# vsBenchPowerSupply.net
KiCad netlist of a schematic drawn in EAGLE
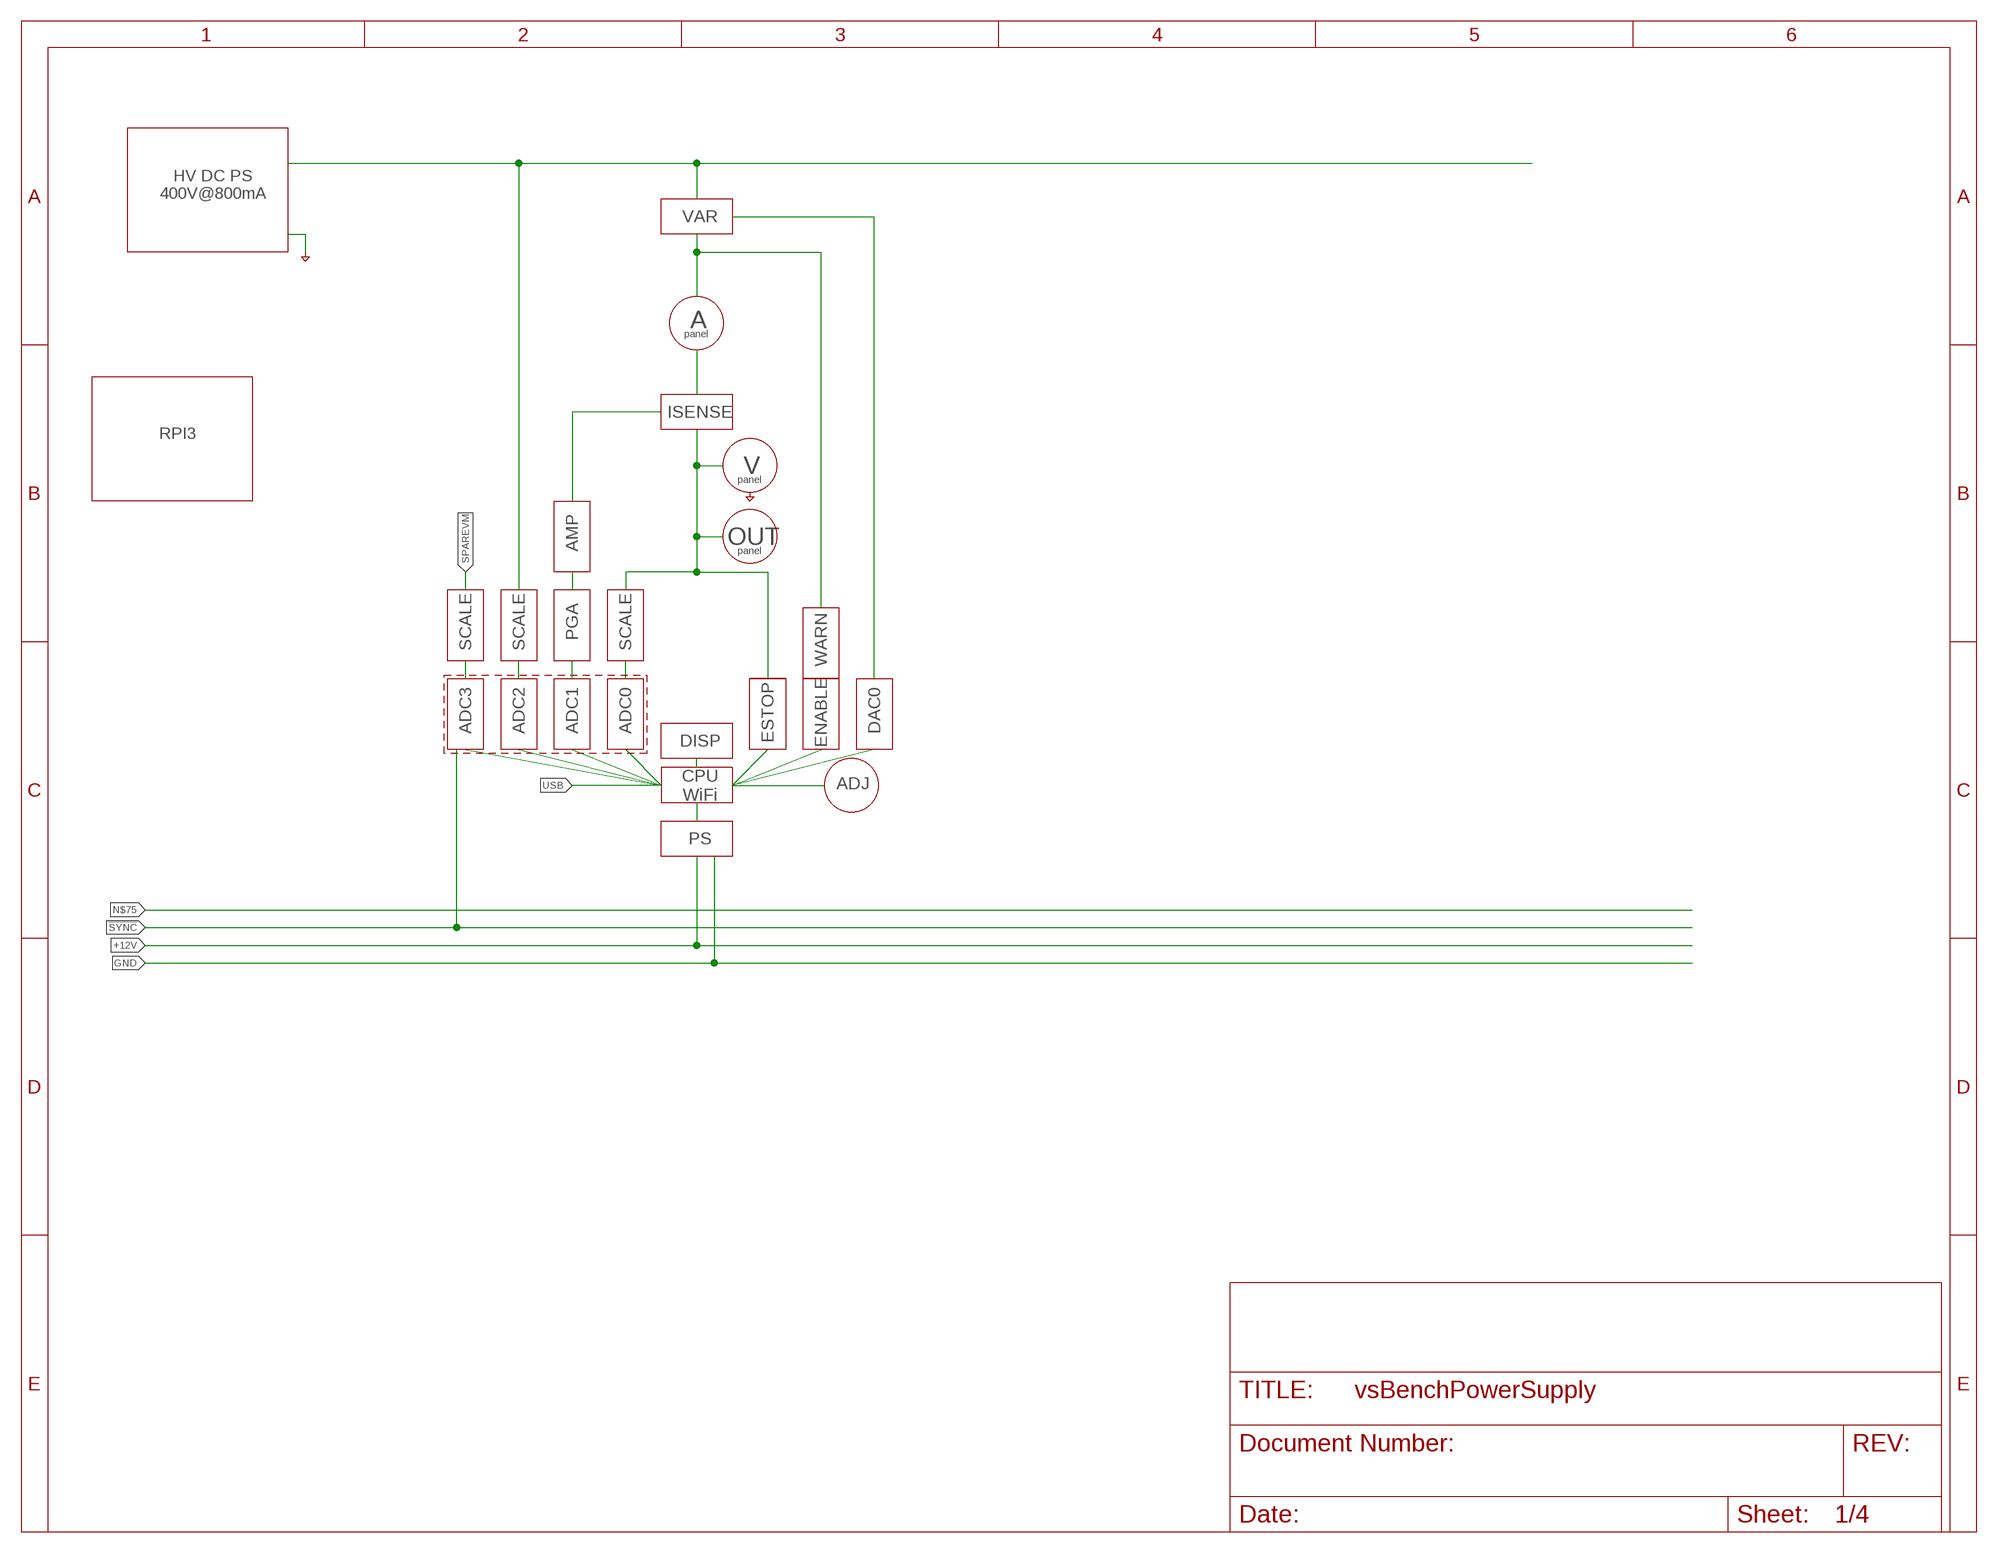
[diagram p0: schematic, sheet 1]
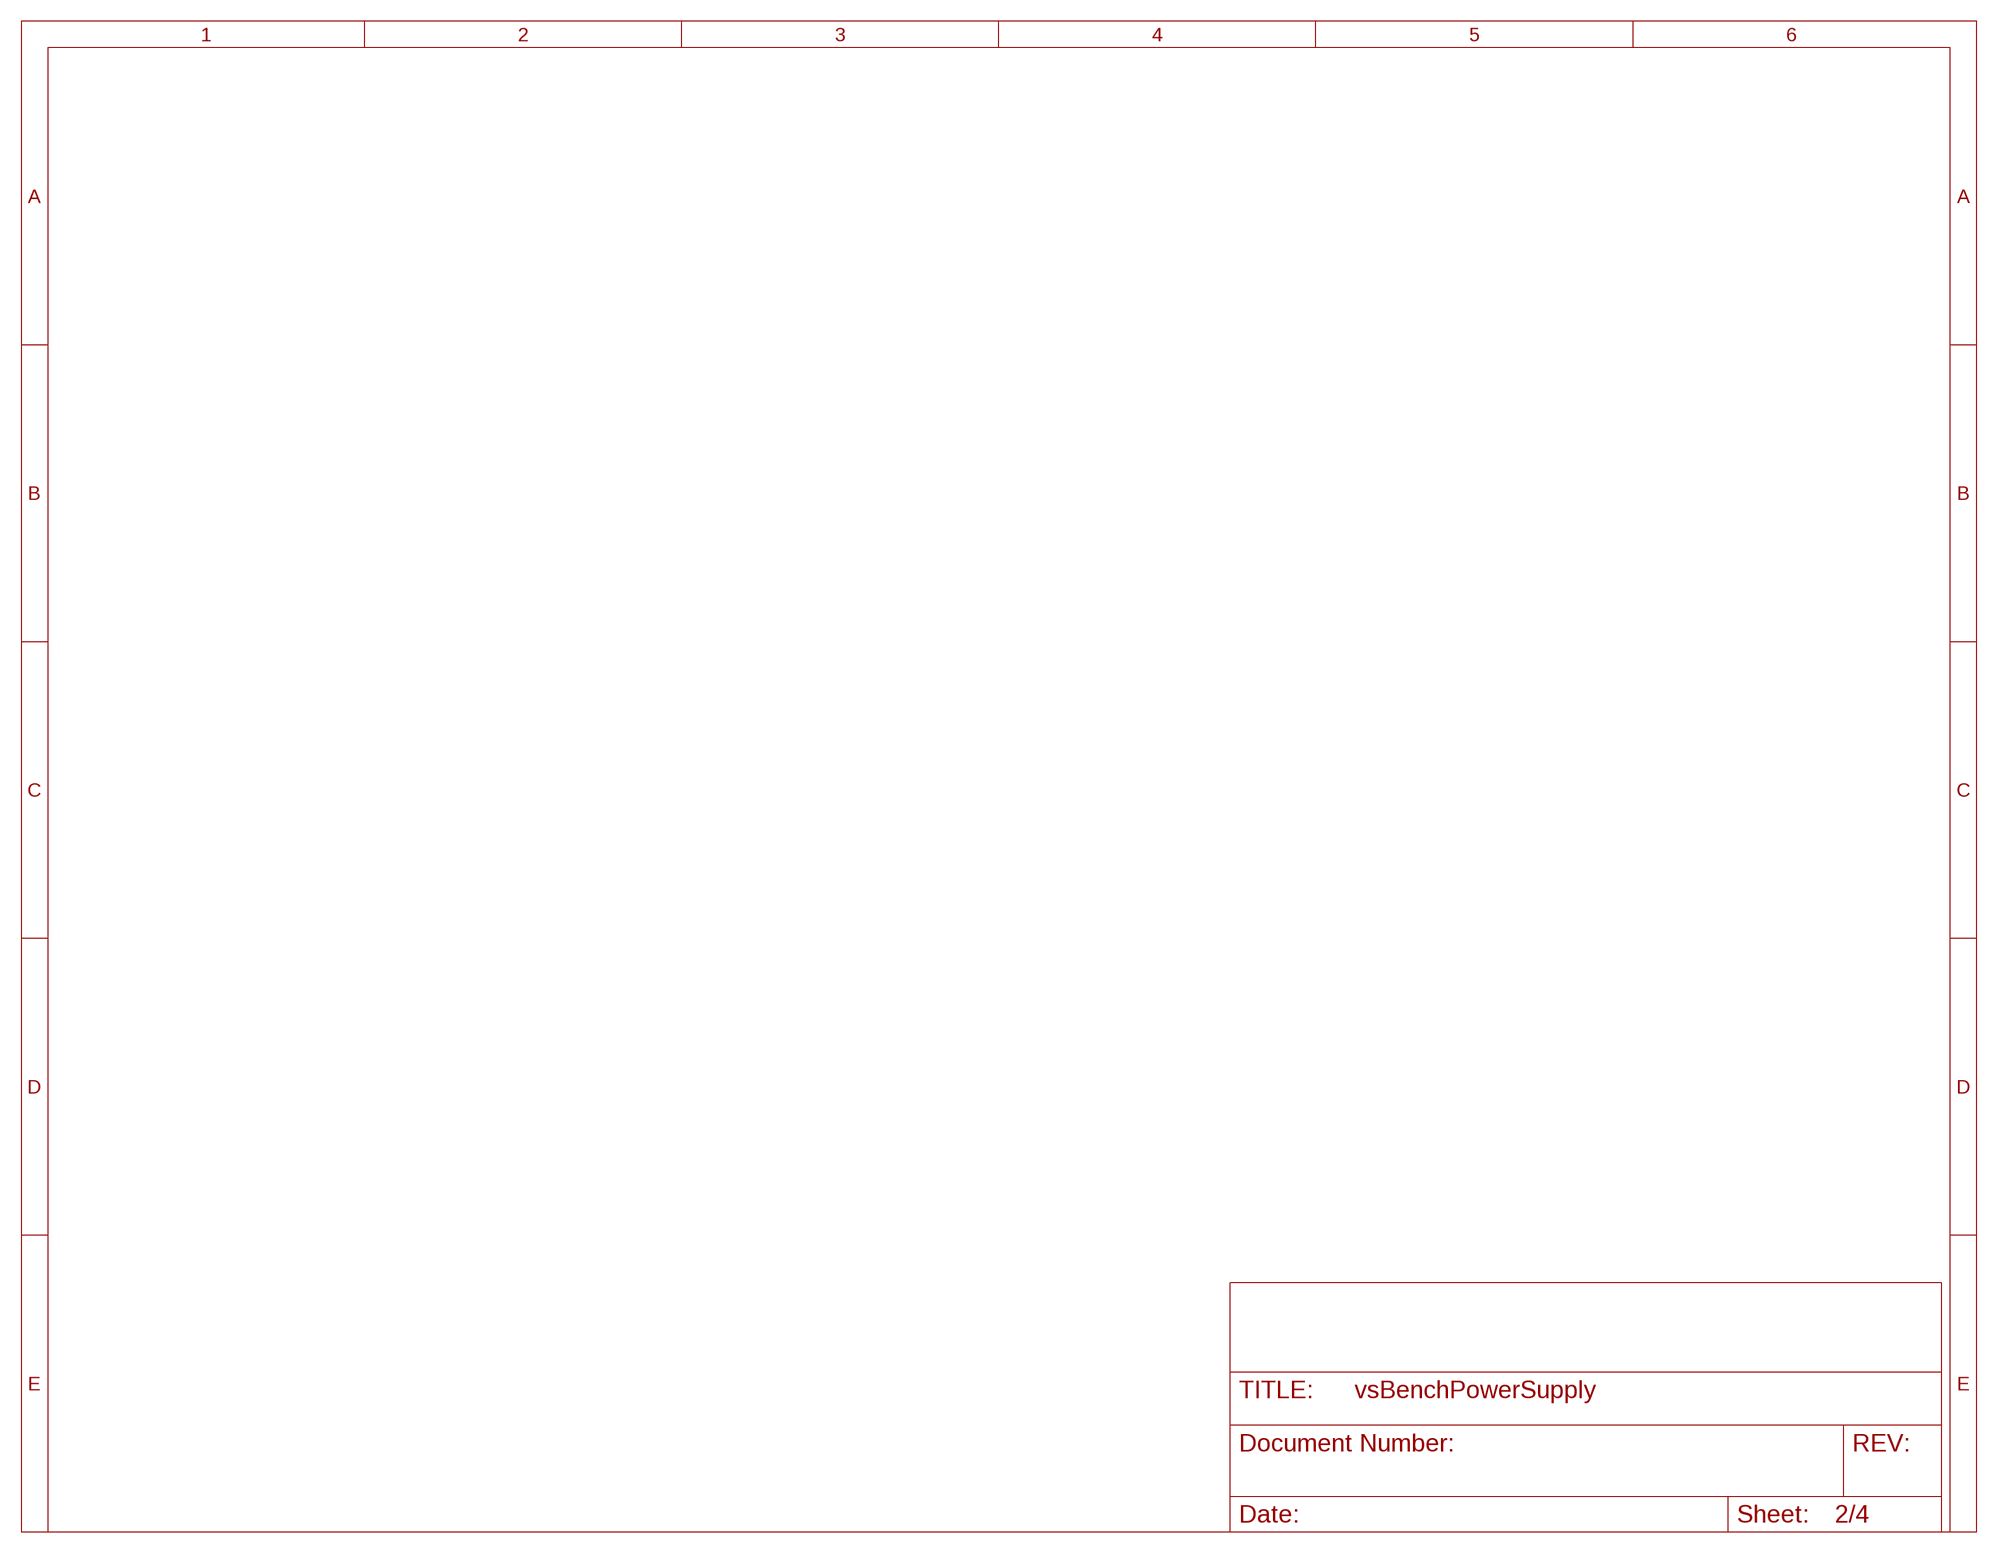
[diagram p1: schematic, sheet 2]
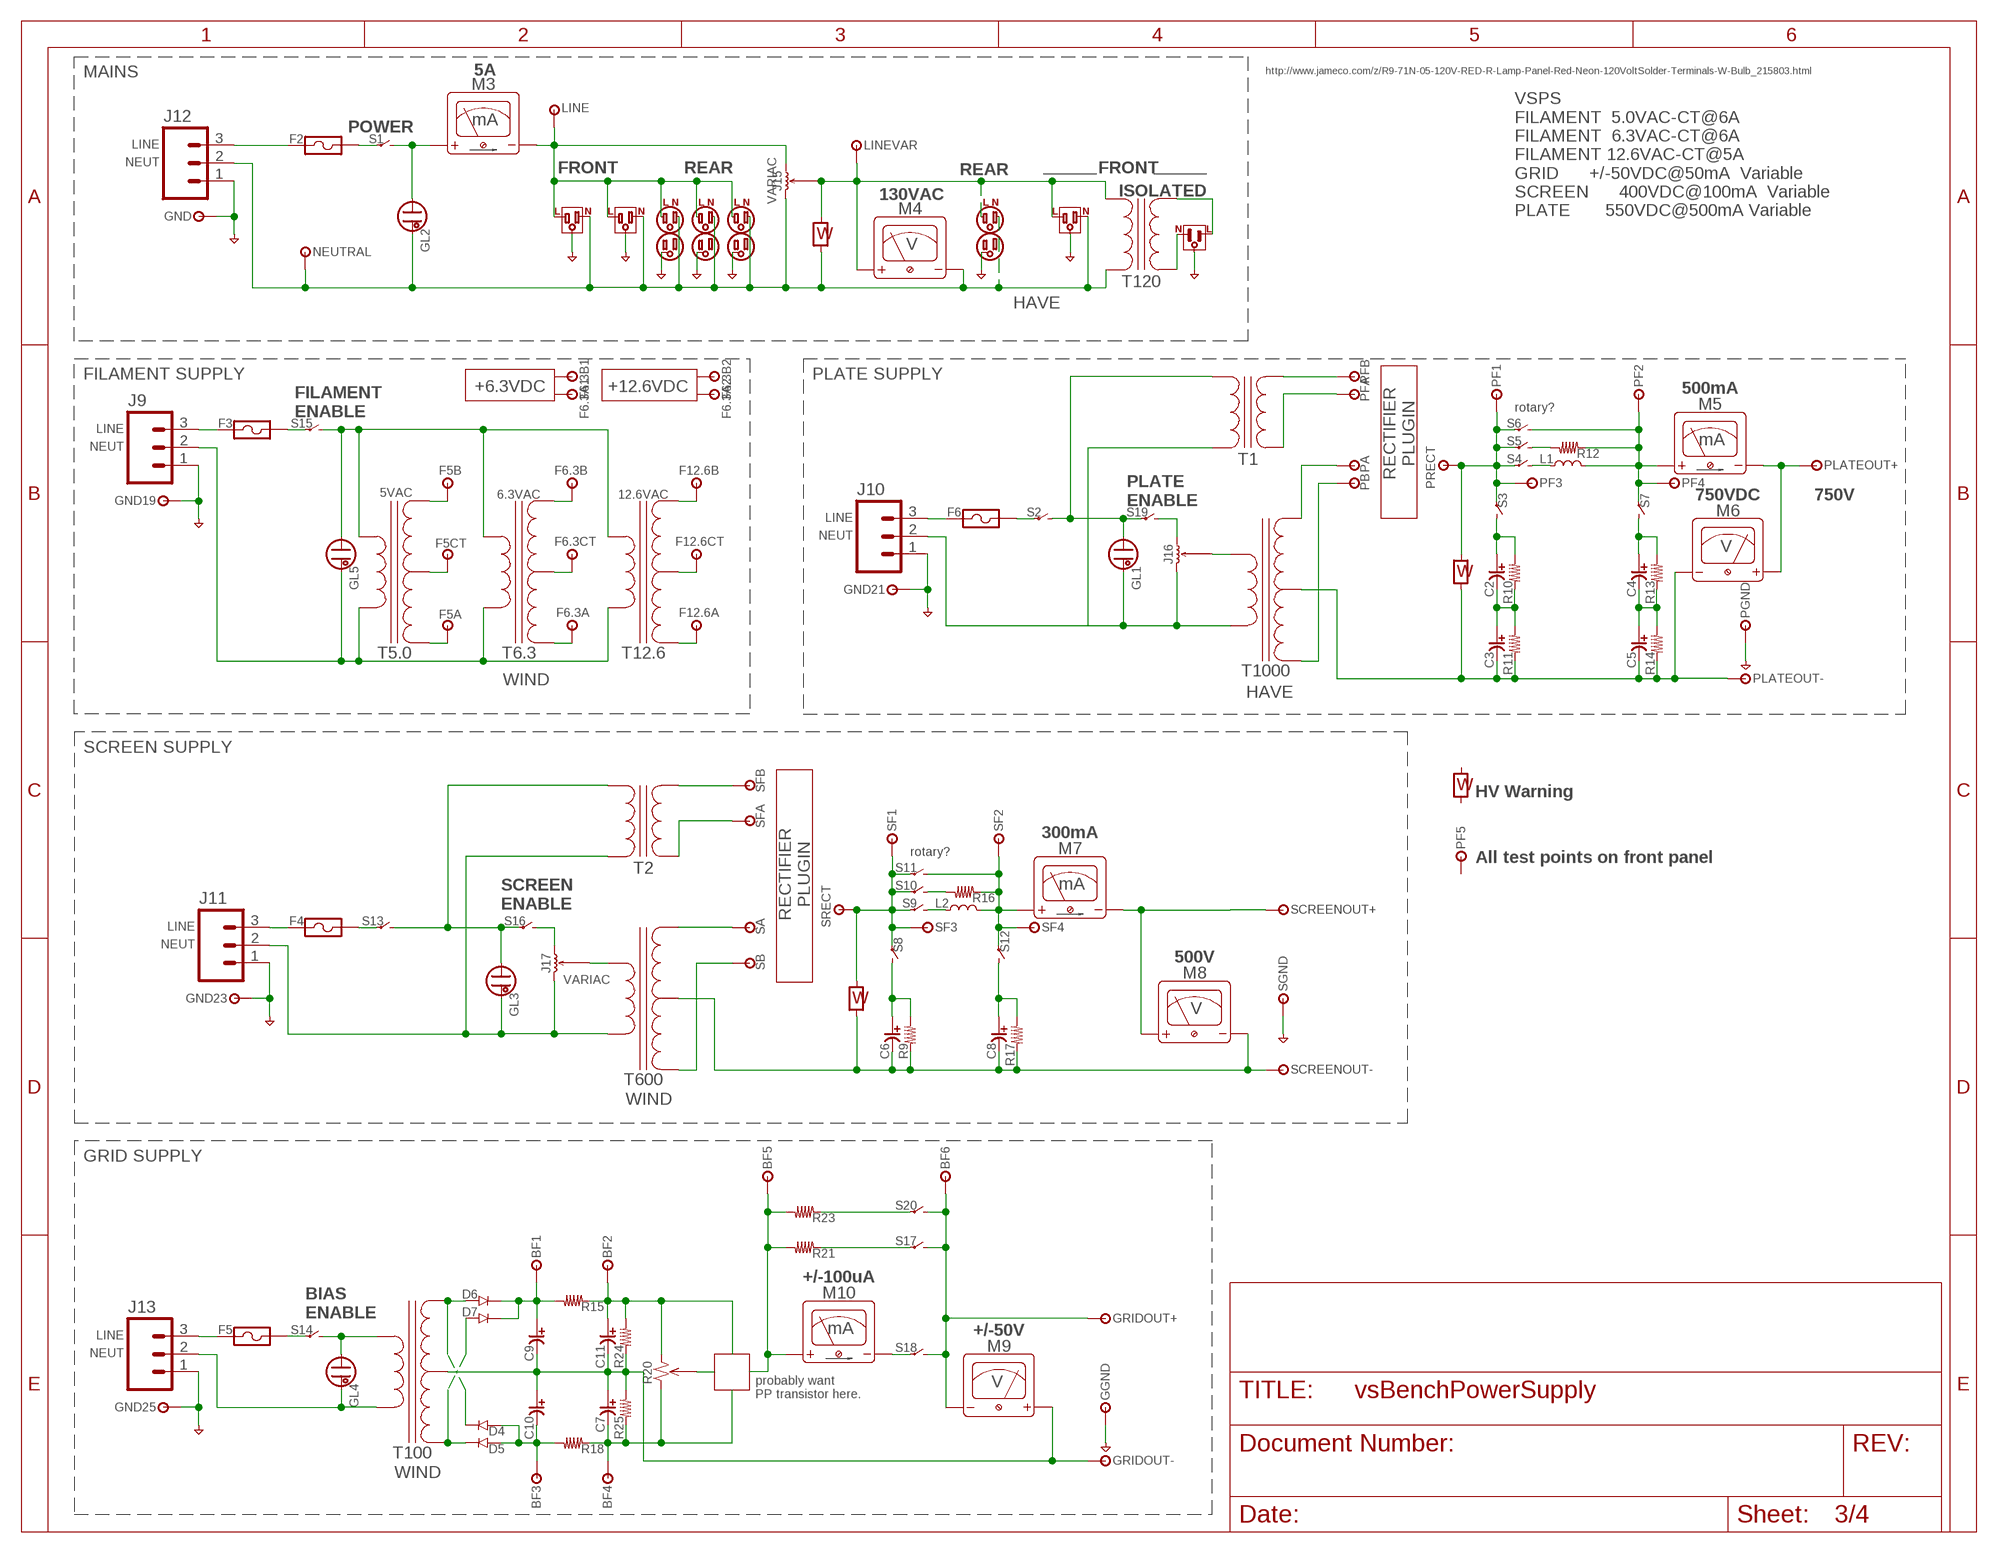
[diagram p2: schematic, sheet 3]
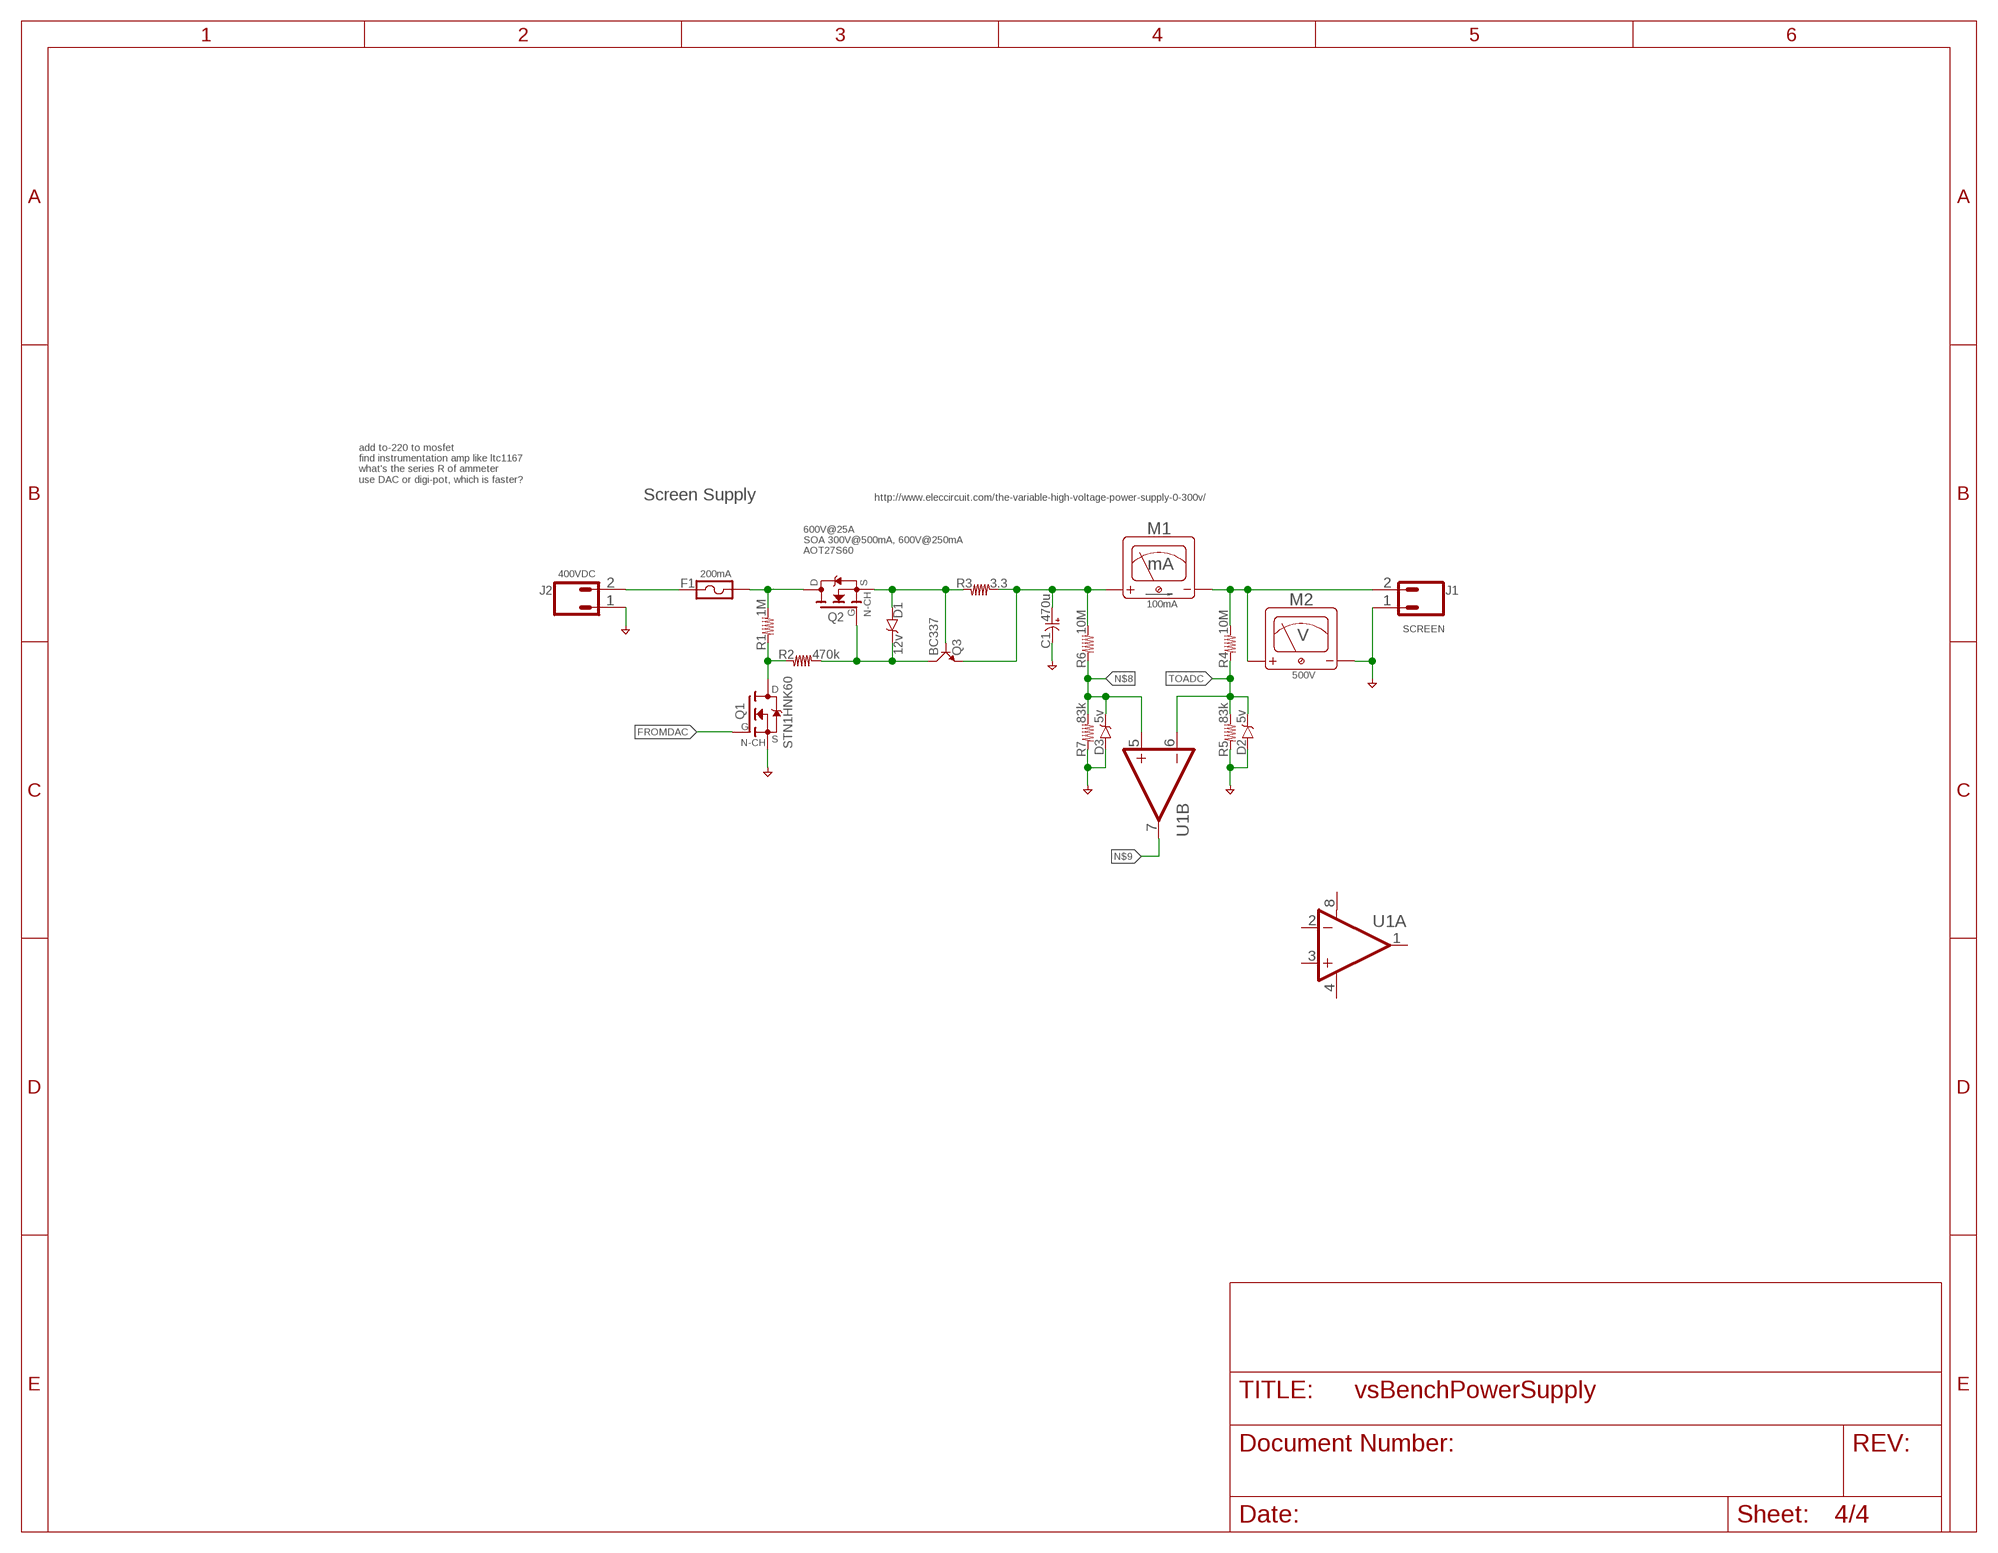
[diagram p3: schematic, sheet 4]

(export (version "E")
  (design (tool "Eeschema 10.0.6"))
  (components
    (comp (ref "BF1")
      (value "TESTPOINTTHRU")
      (footprint "eagle-import:TPTHRU")
      (libsource (lib "eagle-import") (part "TESTPOINTTHRU"))
    )
    (comp (ref "BF2")
      (value "TESTPOINTTHRU")
      (footprint "eagle-import:TPTHRU")
      (libsource (lib "eagle-import") (part "TESTPOINTTHRU"))
    )
    (comp (ref "BF3")
      (value "TESTPOINTTHRU")
      (footprint "eagle-import:TPTHRU")
      (libsource (lib "eagle-import") (part "TESTPOINTTHRU"))
    )
    (comp (ref "BF4")
      (value "TESTPOINTTHRU")
      (footprint "eagle-import:TPTHRU")
      (libsource (lib "eagle-import") (part "TESTPOINTTHRU"))
    )
    (comp (ref "BF5")
      (value "TESTPOINTTHRU")
      (footprint "eagle-import:TPTHRU")
      (libsource (lib "eagle-import") (part "TESTPOINTTHRU"))
    )
    (comp (ref "BF6")
      (value "TESTPOINTTHRU")
      (footprint "eagle-import:TPTHRU")
      (libsource (lib "eagle-import") (part "TESTPOINTTHRU"))
    )
    (comp (ref "C2")
      (value "C-POLARIZED-SMD-E-3MM")
      (footprint "eagle-import:E-3")
      (libsource (lib "eagle-import") (part "C-POLARIZED-SMD-E-3MM"))
    )
    (comp (ref "C3")
      (value "C-POLARIZED-SMD-E-3MM")
      (footprint "eagle-import:E-3")
      (libsource (lib "eagle-import") (part "C-POLARIZED-SMD-E-3MM"))
    )
    (comp (ref "C4")
      (value "C-POLARIZED-SMD-E-3MM")
      (footprint "eagle-import:E-3")
      (libsource (lib "eagle-import") (part "C-POLARIZED-SMD-E-3MM"))
    )
    (comp (ref "C5")
      (value "C-POLARIZED-SMD-E-3MM")
      (footprint "eagle-import:E-3")
      (libsource (lib "eagle-import") (part "C-POLARIZED-SMD-E-3MM"))
    )
    (comp (ref "C6")
      (value "C-POLARIZED-SMD-E-3MM")
      (footprint "eagle-import:E-3")
      (libsource (lib "eagle-import") (part "C-POLARIZED-SMD-E-3MM"))
    )
    (comp (ref "C7")
      (value "C-POLARIZED-SMD-E-3MM")
      (footprint "eagle-import:E-3")
      (libsource (lib "eagle-import") (part "C-POLARIZED-SMD-E-3MM"))
    )
    (comp (ref "C8")
      (value "C-POLARIZED-SMD-E-3MM")
      (footprint "eagle-import:E-3")
      (libsource (lib "eagle-import") (part "C-POLARIZED-SMD-E-3MM"))
    )
    (comp (ref "C9")
      (value "C-POLARIZED-SMD-E-3MM")
      (footprint "eagle-import:E-3")
      (libsource (lib "eagle-import") (part "C-POLARIZED-SMD-E-3MM"))
    )
    (comp (ref "C10")
      (value "C-POLARIZED-SMD-E-3MM")
      (footprint "eagle-import:E-3")
      (libsource (lib "eagle-import") (part "C-POLARIZED-SMD-E-3MM"))
    )
    (comp (ref "C11")
      (value "C-POLARIZED-SMD-E-3MM")
      (footprint "eagle-import:E-3")
      (libsource (lib "eagle-import") (part "C-POLARIZED-SMD-E-3MM"))
    )
    (comp (ref "D4")
      (value "DIODE-1N4148")
      (footprint "eagle-import:DO-35")
      (libsource (lib "eagle-import") (part "DIODE-1N4148"))
    )
    (comp (ref "D5")
      (value "DIODE-1N4148")
      (footprint "eagle-import:DO-35")
      (libsource (lib "eagle-import") (part "DIODE-1N4148"))
    )
    (comp (ref "D6")
      (value "DIODE-1N4148")
      (footprint "eagle-import:DO-35")
      (libsource (lib "eagle-import") (part "DIODE-1N4148"))
    )
    (comp (ref "D7")
      (value "DIODE-1N4148")
      (footprint "eagle-import:DO-35")
      (libsource (lib "eagle-import") (part "DIODE-1N4148"))
    )
    (comp (ref "F2")
      (value "FUSE-HOLDER-3557-2")
      (footprint "eagle-import:3557-2")
      (libsource (lib "eagle-import") (part "FUSE-HOLDER-3557-2"))
    )
    (comp (ref "F3")
      (value "FUSE-HOLDER-3557-2")
      (footprint "eagle-import:3557-2")
      (libsource (lib "eagle-import") (part "FUSE-HOLDER-3557-2"))
    )
    (comp (ref "F4")
      (value "FUSE-HOLDER-3557-2")
      (footprint "eagle-import:3557-2")
      (libsource (lib "eagle-import") (part "FUSE-HOLDER-3557-2"))
    )
    (comp (ref "F5")
      (value "FUSE-HOLDER-3557-2")
      (footprint "eagle-import:3557-2")
      (libsource (lib "eagle-import") (part "FUSE-HOLDER-3557-2"))
    )
    (comp (ref "F5A")
      (value "TESTPOINTTHRU")
      (footprint "eagle-import:TPTHRU")
      (libsource (lib "eagle-import") (part "TESTPOINTTHRU"))
    )
    (comp (ref "F5B")
      (value "TESTPOINTTHRU")
      (footprint "eagle-import:TPTHRU")
      (libsource (lib "eagle-import") (part "TESTPOINTTHRU"))
    )
    (comp (ref "F5CT")
      (value "TESTPOINTTHRU")
      (footprint "eagle-import:TPTHRU")
      (libsource (lib "eagle-import") (part "TESTPOINTTHRU"))
    )
    (comp (ref "F6")
      (value "FUSE-HOLDER-3557-2")
      (footprint "eagle-import:3557-2")
      (libsource (lib "eagle-import") (part "FUSE-HOLDER-3557-2"))
    )
    (comp (ref "F6.3A")
      (value "TESTPOINTTHRU")
      (footprint "eagle-import:TPTHRU")
      (libsource (lib "eagle-import") (part "TESTPOINTTHRU"))
    )
    (comp (ref "F6.3A1")
      (value "TESTPOINTTHRU")
      (footprint "eagle-import:TPTHRU")
      (libsource (lib "eagle-import") (part "TESTPOINTTHRU"))
    )
    (comp (ref "F6.3A2")
      (value "TESTPOINTTHRU")
      (footprint "eagle-import:TPTHRU")
      (libsource (lib "eagle-import") (part "TESTPOINTTHRU"))
    )
    (comp (ref "F6.3B")
      (value "TESTPOINTTHRU")
      (footprint "eagle-import:TPTHRU")
      (libsource (lib "eagle-import") (part "TESTPOINTTHRU"))
    )
    (comp (ref "F6.3B1")
      (value "TESTPOINTTHRU")
      (footprint "eagle-import:TPTHRU")
      (libsource (lib "eagle-import") (part "TESTPOINTTHRU"))
    )
    (comp (ref "F6.3B2")
      (value "TESTPOINTTHRU")
      (footprint "eagle-import:TPTHRU")
      (libsource (lib "eagle-import") (part "TESTPOINTTHRU"))
    )
    (comp (ref "F6.3CT")
      (value "TESTPOINTTHRU")
      (footprint "eagle-import:TPTHRU")
      (libsource (lib "eagle-import") (part "TESTPOINTTHRU"))
    )
    (comp (ref "F12.6A")
      (value "TESTPOINTTHRU")
      (footprint "eagle-import:TPTHRU")
      (libsource (lib "eagle-import") (part "TESTPOINTTHRU"))
    )
    (comp (ref "F12.6B")
      (value "TESTPOINTTHRU")
      (footprint "eagle-import:TPTHRU")
      (libsource (lib "eagle-import") (part "TESTPOINTTHRU"))
    )
    (comp (ref "F12.6CT")
      (value "TESTPOINTTHRU")
      (footprint "eagle-import:TPTHRU")
      (libsource (lib "eagle-import") (part "TESTPOINTTHRU"))
    )
    (comp (ref "GGND")
      (value "TESTPOINTTHRU")
      (footprint "eagle-import:TPTHRU")
      (libsource (lib "eagle-import") (part "TESTPOINTTHRU"))
    )
    (comp (ref "GL1")
      (value "INDICATOR-NEON-BULB-NE2-DRILL")
      (footprint "eagle-import:NE2-NEON-BULB-DRILL")
      (libsource (lib "eagle-import") (part "INDICATOR-NEON-BULB-NE2-DRILL"))
    )
    (comp (ref "GL2")
      (value "INDICATOR-NEON-BULB-NE2-DRILL")
      (footprint "eagle-import:NE2-NEON-BULB-DRILL")
      (libsource (lib "eagle-import") (part "INDICATOR-NEON-BULB-NE2-DRILL"))
    )
    (comp (ref "GL3")
      (value "INDICATOR-NEON-BULB-NE2-DRILL")
      (footprint "eagle-import:NE2-NEON-BULB-DRILL")
      (libsource (lib "eagle-import") (part "INDICATOR-NEON-BULB-NE2-DRILL"))
    )
    (comp (ref "GL4")
      (value "INDICATOR-NEON-BULB-NE2-DRILL")
      (footprint "eagle-import:NE2-NEON-BULB-DRILL")
      (libsource (lib "eagle-import") (part "INDICATOR-NEON-BULB-NE2-DRILL"))
    )
    (comp (ref "GL5")
      (value "INDICATOR-NEON-BULB-NE2-DRILL")
      (footprint "eagle-import:NE2-NEON-BULB-DRILL")
      (libsource (lib "eagle-import") (part "INDICATOR-NEON-BULB-NE2-DRILL"))
    )
    (comp (ref "GND")
      (value "TESTPOINTTHRU")
      (footprint "eagle-import:TPTHRU")
      (libsource (lib "eagle-import") (part "TESTPOINTTHRU"))
    )
    (comp (ref "GND19")
      (value "TESTPOINTTHRU")
      (footprint "eagle-import:TPTHRU")
      (libsource (lib "eagle-import") (part "TESTPOINTTHRU"))
    )
    (comp (ref "GND21")
      (value "TESTPOINTTHRU")
      (footprint "eagle-import:TPTHRU")
      (libsource (lib "eagle-import") (part "TESTPOINTTHRU"))
    )
    (comp (ref "GND23")
      (value "TESTPOINTTHRU")
      (footprint "eagle-import:TPTHRU")
      (libsource (lib "eagle-import") (part "TESTPOINTTHRU"))
    )
    (comp (ref "GND25")
      (value "TESTPOINTTHRU")
      (footprint "eagle-import:TPTHRU")
      (libsource (lib "eagle-import") (part "TESTPOINTTHRU"))
    )
    (comp (ref "GRIDOUT+")
      (value "TESTPOINTTHRU")
      (footprint "eagle-import:TPTHRU")
      (libsource (lib "eagle-import") (part "TESTPOINTTHRU"))
    )
    (comp (ref "GRIDOUT-")
      (value "TESTPOINTTHRU")
      (footprint "eagle-import:TPTHRU")
      (libsource (lib "eagle-import") (part "TESTPOINTTHRU"))
    )
    (comp (ref "J3")
      (value "OUTLET-RECEPTABLE-SINGLE")
      (footprint "eagle-import:CONN-3.81MM-KF2EDG-3")
      (libsource (lib "eagle-import") (part "OUTLET-RECEPTABLE-SINGLE"))
    )
    (comp (ref "J4")
      (value "OUTLET-RECEPTABLE-SINGLE")
      (footprint "eagle-import:CONN-3.81MM-KF2EDG-3")
      (libsource (lib "eagle-import") (part "OUTLET-RECEPTABLE-SINGLE"))
    )
    (comp (ref "J5")
      (value "OUTLET-RECEPTABLE-SINGLE")
      (footprint "eagle-import:CONN-3.81MM-KF2EDG-3")
      (libsource (lib "eagle-import") (part "OUTLET-RECEPTABLE-SINGLE"))
    )
    (comp (ref "J6")
      (value "METER-PANEL-HV-WARNING")
      (footprint "eagle-import:CONN-.100-2")
      (libsource (lib "eagle-import") (part "METER-PANEL-HV-WARNING"))
    )
    (comp (ref "J7")
      (value "METER-PANEL-HV-WARNING")
      (footprint "eagle-import:CONN-.100-2")
      (libsource (lib "eagle-import") (part "METER-PANEL-HV-WARNING"))
    )
    (comp (ref "J8")
      (value "METER-PANEL-HV-WARNING")
      (footprint "eagle-import:CONN-.100-2")
      (libsource (lib "eagle-import") (part "METER-PANEL-HV-WARNING"))
    )
    (comp (ref "J9")
      (value "CONN-03-3.81MM-PLUGIN-SCREW")
      (footprint "eagle-import:CONN-3.81MM-KF2EDG-3")
      (libsource (lib "eagle-import") (part "CONN-03-3.81MM-PLUGIN-SCREW"))
    )
    (comp (ref "J10")
      (value "CONN-03-3.81MM-PLUGIN-SCREW")
      (footprint "eagle-import:CONN-3.81MM-KF2EDG-3")
      (libsource (lib "eagle-import") (part "CONN-03-3.81MM-PLUGIN-SCREW"))
    )
    (comp (ref "J11")
      (value "CONN-03-3.81MM-PLUGIN-SCREW")
      (footprint "eagle-import:CONN-3.81MM-KF2EDG-3")
      (libsource (lib "eagle-import") (part "CONN-03-3.81MM-PLUGIN-SCREW"))
    )
    (comp (ref "J12")
      (value "CONN-03-3.81MM-PLUGIN-SCREW")
      (footprint "eagle-import:CONN-3.81MM-KF2EDG-3")
      (libsource (lib "eagle-import") (part "CONN-03-3.81MM-PLUGIN-SCREW"))
    )
    (comp (ref "J13")
      (value "CONN-03-3.81MM-PLUGIN-SCREW")
      (footprint "eagle-import:CONN-3.81MM-KF2EDG-3")
      (libsource (lib "eagle-import") (part "CONN-03-3.81MM-PLUGIN-SCREW"))
    )
    (comp (ref "J14")
      (value "METER-PANEL-HV-WARNING")
      (footprint "eagle-import:CONN-.100-2")
      (libsource (lib "eagle-import") (part "METER-PANEL-HV-WARNING"))
    )
    (comp (ref "J15")
      (value "VARIAC")
      (footprint "eagle-import:CONN-.100-3")
      (libsource (lib "eagle-import") (part "VARIAC"))
    )
    (comp (ref "J16")
      (value "VARIAC")
      (footprint "eagle-import:CONN-.100-3")
      (libsource (lib "eagle-import") (part "VARIAC"))
    )
    (comp (ref "J17")
      (value "VARIAC")
      (footprint "eagle-import:CONN-.100-3")
      (libsource (lib "eagle-import") (part "VARIAC"))
    )
    (comp (ref "J18")
      (value "OUTLET-RECEPTABLE-SINGLE")
      (footprint "eagle-import:CONN-3.81MM-KF2EDG-3")
      (libsource (lib "eagle-import") (part "OUTLET-RECEPTABLE-SINGLE"))
    )
    (comp (ref "L1")
      (value "INDUCTOR-0805")
      (footprint "eagle-import:R0805")
      (libsource (lib "eagle-import") (part "INDUCTOR-0805"))
    )
    (comp (ref "L2")
      (value "INDUCTOR-0805")
      (footprint "eagle-import:R0805")
      (libsource (lib "eagle-import") (part "INDUCTOR-0805"))
    )
    (comp (ref "LINE")
      (value "TESTPOINTTHRU")
      (footprint "eagle-import:TPTHRU")
      (libsource (lib "eagle-import") (part "TESTPOINTTHRU"))
    )
    (comp (ref "LINEVAR")
      (value "TESTPOINTTHRU")
      (footprint "eagle-import:TPTHRU")
      (libsource (lib "eagle-import") (part "TESTPOINTTHRU"))
    )
    (comp (ref "M3")
      (value "METER-PANEL-ANALOG-CURRENT-PLUGIN-3.81MM")
      (footprint "eagle-import:CONN-3.81MM-KF2EDG-2")
      (libsource (lib "eagle-import") (part "METER-PANEL-ANALOG-CURRENT-PLUGIN-3.81MM"))
    )
    (comp (ref "M4")
      (value "METER-PANEL-ANALOG-VOLTAGE-PLUGIN-3.81MM")
      (footprint "eagle-import:CONN-3.81MM-KF2EDG-2")
      (libsource (lib "eagle-import") (part "METER-PANEL-ANALOG-VOLTAGE-PLUGIN-3.81MM"))
    )
    (comp (ref "M5")
      (value "METER-PANEL-ANALOG-CURRENT-PLUGIN-3.81MM")
      (footprint "eagle-import:CONN-3.81MM-KF2EDG-2")
      (libsource (lib "eagle-import") (part "METER-PANEL-ANALOG-CURRENT-PLUGIN-3.81MM"))
    )
    (comp (ref "M6")
      (value "METER-PANEL-ANALOG-VOLTAGE-PLUGIN-3.81MM")
      (footprint "eagle-import:CONN-3.81MM-KF2EDG-2")
      (libsource (lib "eagle-import") (part "METER-PANEL-ANALOG-VOLTAGE-PLUGIN-3.81MM"))
    )
    (comp (ref "M7")
      (value "METER-PANEL-ANALOG-CURRENT-PLUGIN-3.81MM")
      (footprint "eagle-import:CONN-3.81MM-KF2EDG-2")
      (libsource (lib "eagle-import") (part "METER-PANEL-ANALOG-CURRENT-PLUGIN-3.81MM"))
    )
    (comp (ref "M8")
      (value "METER-PANEL-ANALOG-VOLTAGE-PLUGIN-3.81MM")
      (footprint "eagle-import:CONN-3.81MM-KF2EDG-2")
      (libsource (lib "eagle-import") (part "METER-PANEL-ANALOG-VOLTAGE-PLUGIN-3.81MM"))
    )
    (comp (ref "M9")
      (value "METER-PANEL-ANALOG-VOLTAGE-PLUGIN-3.81MM")
      (footprint "eagle-import:CONN-3.81MM-KF2EDG-2")
      (libsource (lib "eagle-import") (part "METER-PANEL-ANALOG-VOLTAGE-PLUGIN-3.81MM"))
    )
    (comp (ref "M10")
      (value "METER-PANEL-ANALOG-CURRENT-PLUGIN-3.81MM")
      (footprint "eagle-import:CONN-3.81MM-KF2EDG-2")
      (libsource (lib "eagle-import") (part "METER-PANEL-ANALOG-CURRENT-PLUGIN-3.81MM"))
    )
    (comp (ref "NEUTRAL")
      (value "TESTPOINTTHRU")
      (footprint "eagle-import:TPTHRU")
      (libsource (lib "eagle-import") (part "TESTPOINTTHRU"))
    )
    (comp (ref "PA")
      (value "TESTPOINTTHRU")
      (footprint "eagle-import:TPTHRU")
      (libsource (lib "eagle-import") (part "TESTPOINTTHRU"))
    )
    (comp (ref "PB")
      (value "TESTPOINTTHRU")
      (footprint "eagle-import:TPTHRU")
      (libsource (lib "eagle-import") (part "TESTPOINTTHRU"))
    )
    (comp (ref "PF1")
      (value "TESTPOINTTHRU")
      (footprint "eagle-import:TPTHRU")
      (libsource (lib "eagle-import") (part "TESTPOINTTHRU"))
    )
    (comp (ref "PF2")
      (value "TESTPOINTTHRU")
      (footprint "eagle-import:TPTHRU")
      (libsource (lib "eagle-import") (part "TESTPOINTTHRU"))
    )
    (comp (ref "PF3")
      (value "TESTPOINTTHRU")
      (footprint "eagle-import:TPTHRU")
      (libsource (lib "eagle-import") (part "TESTPOINTTHRU"))
    )
    (comp (ref "PF4")
      (value "TESTPOINTTHRU")
      (footprint "eagle-import:TPTHRU")
      (libsource (lib "eagle-import") (part "TESTPOINTTHRU"))
    )
    (comp (ref "PF5")
      (value "TESTPOINTTHRU")
      (footprint "eagle-import:TPTHRU")
      (libsource (lib "eagle-import") (part "TESTPOINTTHRU"))
    )
    (comp (ref "PFA")
      (value "TESTPOINTTHRU")
      (footprint "eagle-import:TPTHRU")
      (libsource (lib "eagle-import") (part "TESTPOINTTHRU"))
    )
    (comp (ref "PFB")
      (value "TESTPOINTTHRU")
      (footprint "eagle-import:TPTHRU")
      (libsource (lib "eagle-import") (part "TESTPOINTTHRU"))
    )
    (comp (ref "PGND")
      (value "TESTPOINTTHRU")
      (footprint "eagle-import:TPTHRU")
      (libsource (lib "eagle-import") (part "TESTPOINTTHRU"))
    )
    (comp (ref "PLATEOUT+")
      (value "TESTPOINTTHRU")
      (footprint "eagle-import:TPTHRU")
      (libsource (lib "eagle-import") (part "TESTPOINTTHRU"))
    )
    (comp (ref "PLATEOUT-")
      (value "TESTPOINTTHRU")
      (footprint "eagle-import:TPTHRU")
      (libsource (lib "eagle-import") (part "TESTPOINTTHRU"))
    )
    (comp (ref "PRECT")
      (value "TESTPOINTTHRU")
      (footprint "eagle-import:TPTHRU")
      (libsource (lib "eagle-import") (part "TESTPOINTTHRU"))
    )
    (comp (ref "R9")
      (value "R-0402")
      (footprint "eagle-import:R0402")
      (libsource (lib "eagle-import") (part "R-0402"))
    )
    (comp (ref "R10")
      (value "R-0402")
      (footprint "eagle-import:R0402")
      (libsource (lib "eagle-import") (part "R-0402"))
    )
    (comp (ref "R11")
      (value "R-0402")
      (footprint "eagle-import:R0402")
      (libsource (lib "eagle-import") (part "R-0402"))
    )
    (comp (ref "R12")
      (value "R-0402")
      (footprint "eagle-import:R0402")
      (libsource (lib "eagle-import") (part "R-0402"))
    )
    (comp (ref "R13")
      (value "R-0402")
      (footprint "eagle-import:R0402")
      (libsource (lib "eagle-import") (part "R-0402"))
    )
    (comp (ref "R14")
      (value "R-0402")
      (footprint "eagle-import:R0402")
      (libsource (lib "eagle-import") (part "R-0402"))
    )
    (comp (ref "R15")
      (value "R-0402")
      (footprint "eagle-import:R0402")
      (libsource (lib "eagle-import") (part "R-0402"))
    )
    (comp (ref "R16")
      (value "R-0402")
      (footprint "eagle-import:R0402")
      (libsource (lib "eagle-import") (part "R-0402"))
    )
    (comp (ref "R17")
      (value "R-0402")
      (footprint "eagle-import:R0402")
      (libsource (lib "eagle-import") (part "R-0402"))
    )
    (comp (ref "R18")
      (value "R-0402")
      (footprint "eagle-import:R0402")
      (libsource (lib "eagle-import") (part "R-0402"))
    )
    (comp (ref "R20")
      (value "POTENTIOMETER")
      (footprint "eagle-import:CONN-.100-3")
      (libsource (lib "eagle-import") (part "POTENTIOMETER"))
    )
    (comp (ref "R21")
      (value "R-0402")
      (footprint "eagle-import:R0402")
      (libsource (lib "eagle-import") (part "R-0402"))
    )
    (comp (ref "R23")
      (value "R-0402")
      (footprint "eagle-import:R0402")
      (libsource (lib "eagle-import") (part "R-0402"))
    )
    (comp (ref "R24")
      (value "R-0402")
      (footprint "eagle-import:R0402")
      (libsource (lib "eagle-import") (part "R-0402"))
    )
    (comp (ref "R25")
      (value "R-0402")
      (footprint "eagle-import:R0402")
      (libsource (lib "eagle-import") (part "R-0402"))
    )
    (comp (ref "S1")
      (value "SWITCH-PANEL-SPST")
      (footprint "eagle-import:CONN-.100-2")
      (libsource (lib "eagle-import") (part "SWITCH-PANEL-SPST"))
    )
    (comp (ref "S2")
      (value "SWITCH-PANEL-SPST")
      (footprint "eagle-import:CONN-.100-2")
      (libsource (lib "eagle-import") (part "SWITCH-PANEL-SPST"))
    )
    (comp (ref "S3")
      (value "SWITCH-PANEL-SPST")
      (footprint "eagle-import:CONN-.100-2")
      (libsource (lib "eagle-import") (part "SWITCH-PANEL-SPST"))
    )
    (comp (ref "S4")
      (value "SWITCH-PANEL-SPST")
      (footprint "eagle-import:CONN-.100-2")
      (libsource (lib "eagle-import") (part "SWITCH-PANEL-SPST"))
    )
    (comp (ref "S5")
      (value "SWITCH-PANEL-SPST")
      (footprint "eagle-import:CONN-.100-2")
      (libsource (lib "eagle-import") (part "SWITCH-PANEL-SPST"))
    )
    (comp (ref "S6")
      (value "SWITCH-PANEL-SPST")
      (footprint "eagle-import:CONN-.100-2")
      (libsource (lib "eagle-import") (part "SWITCH-PANEL-SPST"))
    )
    (comp (ref "S7")
      (value "SWITCH-PANEL-SPST")
      (footprint "eagle-import:CONN-.100-2")
      (libsource (lib "eagle-import") (part "SWITCH-PANEL-SPST"))
    )
    (comp (ref "S8")
      (value "SWITCH-PANEL-SPST")
      (footprint "eagle-import:CONN-.100-2")
      (libsource (lib "eagle-import") (part "SWITCH-PANEL-SPST"))
    )
    (comp (ref "S9")
      (value "SWITCH-PANEL-SPST")
      (footprint "eagle-import:CONN-.100-2")
      (libsource (lib "eagle-import") (part "SWITCH-PANEL-SPST"))
    )
    (comp (ref "S10")
      (value "SWITCH-PANEL-SPST")
      (footprint "eagle-import:CONN-.100-2")
      (libsource (lib "eagle-import") (part "SWITCH-PANEL-SPST"))
    )
    (comp (ref "S11")
      (value "SWITCH-PANEL-SPST")
      (footprint "eagle-import:CONN-.100-2")
      (libsource (lib "eagle-import") (part "SWITCH-PANEL-SPST"))
    )
    (comp (ref "S12")
      (value "SWITCH-PANEL-SPST")
      (footprint "eagle-import:CONN-.100-2")
      (libsource (lib "eagle-import") (part "SWITCH-PANEL-SPST"))
    )
    (comp (ref "S13")
      (value "SWITCH-PANEL-SPST")
      (footprint "eagle-import:CONN-.100-2")
      (libsource (lib "eagle-import") (part "SWITCH-PANEL-SPST"))
    )
    (comp (ref "S14")
      (value "SWITCH-PANEL-SPST")
      (footprint "eagle-import:CONN-.100-2")
      (libsource (lib "eagle-import") (part "SWITCH-PANEL-SPST"))
    )
    (comp (ref "S15")
      (value "SWITCH-PANEL-SPST")
      (footprint "eagle-import:CONN-.100-2")
      (libsource (lib "eagle-import") (part "SWITCH-PANEL-SPST"))
    )
    (comp (ref "S16")
      (value "SWITCH-PANEL-SPST")
      (footprint "eagle-import:CONN-.100-2")
      (libsource (lib "eagle-import") (part "SWITCH-PANEL-SPST"))
    )
    (comp (ref "S17")
      (value "SWITCH-PANEL-SPST")
      (footprint "eagle-import:CONN-.100-2")
      (libsource (lib "eagle-import") (part "SWITCH-PANEL-SPST"))
    )
    (comp (ref "S18")
      (value "SWITCH-PANEL-SPST")
      (footprint "eagle-import:CONN-.100-2")
      (libsource (lib "eagle-import") (part "SWITCH-PANEL-SPST"))
    )
    (comp (ref "S19")
      (value "SWITCH-PANEL-SPST")
      (footprint "eagle-import:CONN-.100-2")
      (libsource (lib "eagle-import") (part "SWITCH-PANEL-SPST"))
    )
    (comp (ref "S20")
      (value "SWITCH-PANEL-SPST")
      (footprint "eagle-import:CONN-.100-2")
      (libsource (lib "eagle-import") (part "SWITCH-PANEL-SPST"))
    )
    (comp (ref "SA")
      (value "TESTPOINTTHRU")
      (footprint "eagle-import:TPTHRU")
      (libsource (lib "eagle-import") (part "TESTPOINTTHRU"))
    )
    (comp (ref "SB")
      (value "TESTPOINTTHRU")
      (footprint "eagle-import:TPTHRU")
      (libsource (lib "eagle-import") (part "TESTPOINTTHRU"))
    )
    (comp (ref "SCREENOUT+")
      (value "TESTPOINTTHRU")
      (footprint "eagle-import:TPTHRU")
      (libsource (lib "eagle-import") (part "TESTPOINTTHRU"))
    )
    (comp (ref "SCREENOUT-")
      (value "TESTPOINTTHRU")
      (footprint "eagle-import:TPTHRU")
      (libsource (lib "eagle-import") (part "TESTPOINTTHRU"))
    )
    (comp (ref "SF1")
      (value "TESTPOINTTHRU")
      (footprint "eagle-import:TPTHRU")
      (libsource (lib "eagle-import") (part "TESTPOINTTHRU"))
    )
    (comp (ref "SF2")
      (value "TESTPOINTTHRU")
      (footprint "eagle-import:TPTHRU")
      (libsource (lib "eagle-import") (part "TESTPOINTTHRU"))
    )
    (comp (ref "SF3")
      (value "TESTPOINTTHRU")
      (footprint "eagle-import:TPTHRU")
      (libsource (lib "eagle-import") (part "TESTPOINTTHRU"))
    )
    (comp (ref "SF4")
      (value "TESTPOINTTHRU")
      (footprint "eagle-import:TPTHRU")
      (libsource (lib "eagle-import") (part "TESTPOINTTHRU"))
    )
    (comp (ref "SFA")
      (value "TESTPOINTTHRU")
      (footprint "eagle-import:TPTHRU")
      (libsource (lib "eagle-import") (part "TESTPOINTTHRU"))
    )
    (comp (ref "SFB")
      (value "TESTPOINTTHRU")
      (footprint "eagle-import:TPTHRU")
      (libsource (lib "eagle-import") (part "TESTPOINTTHRU"))
    )
    (comp (ref "SGND")
      (value "TESTPOINTTHRU")
      (footprint "eagle-import:TPTHRU")
      (libsource (lib "eagle-import") (part "TESTPOINTTHRU"))
    )
    (comp (ref "SRECT")
      (value "TESTPOINTTHRU")
      (footprint "eagle-import:TPTHRU")
      (libsource (lib "eagle-import") (part "TESTPOINTTHRU"))
    )
    (comp (ref "T1")
      (value "TRANSFORMER-2-2")
      (footprint "eagle-import:TRANSFORMER-4-2-G")
      (libsource (lib "eagle-import") (part "TRANSFORMER-2-2"))
    )
    (comp (ref "T2")
      (value "TRANSFORMER-2-2")
      (footprint "eagle-import:TRANSFORMER-4-2-G")
      (libsource (lib "eagle-import") (part "TRANSFORMER-2-2"))
    )
    (comp (ref "T5.0")
      (value "TRANSFORMER-3-2")
      (footprint "eagle-import:CONN-.100-5")
      (libsource (lib "eagle-import") (part "TRANSFORMER-3-2"))
    )
    (comp (ref "T6.3")
      (value "TRANSFORMER-3-2")
      (footprint "eagle-import:CONN-.100-5")
      (libsource (lib "eagle-import") (part "TRANSFORMER-3-2"))
    )
    (comp (ref "T12.6")
      (value "TRANSFORMER-3-2")
      (footprint "eagle-import:CONN-.100-5")
      (libsource (lib "eagle-import") (part "TRANSFORMER-3-2"))
    )
    (comp (ref "T100")
      (value "TRANSFORMER-3-2")
      (footprint "eagle-import:CONN-.100-5")
      (libsource (lib "eagle-import") (part "TRANSFORMER-3-2"))
    )
    (comp (ref "T120")
      (value "TRANSFORMER-2-2")
      (footprint "eagle-import:TRANSFORMER-4-2-G")
      (libsource (lib "eagle-import") (part "TRANSFORMER-2-2"))
    )
    (comp (ref "T600")
      (value "TRANSFORMER-3-2")
      (footprint "eagle-import:CONN-.100-5")
      (libsource (lib "eagle-import") (part "TRANSFORMER-3-2"))
    )
    (comp (ref "T1000")
      (value "TRANSFORMER-3-2")
      (footprint "eagle-import:CONN-.100-5")
      (libsource (lib "eagle-import") (part "TRANSFORMER-3-2"))
    )
    (comp (ref "U$1")
      (value "OUTLET-RECEPTACLE")
      (footprint "eagle-import:CONN-3.81MM-KF2EDG-3")
      (libsource (lib "eagle-import") (part "OUTLET-RECEPTACLE"))
    )
    (comp (ref "U$2")
      (value "OUTLET-RECEPTACLE")
      (footprint "eagle-import:CONN-3.81MM-KF2EDG-3")
      (libsource (lib "eagle-import") (part "OUTLET-RECEPTACLE"))
    )
    (comp (ref "U$3")
      (value "OUTLET-RECEPTACLE")
      (footprint "eagle-import:CONN-3.81MM-KF2EDG-3")
      (libsource (lib "eagle-import") (part "OUTLET-RECEPTACLE"))
    )
    (comp (ref "U$4")
      (value "OUTLET-RECEPTACLE")
      (footprint "eagle-import:CONN-3.81MM-KF2EDG-3")
      (libsource (lib "eagle-import") (part "OUTLET-RECEPTACLE"))
    )
    (comp (ref "C1")
      (value "470u")
      (footprint "eagle-import:E5-10,5")
      (libsource (lib "eagle-import") (part "C-E5-10.5"))
    )
    (comp (ref "D1")
      (value "12v")
      (footprint "eagle-import:SOD-323")
      (libsource (lib "eagle-import") (part "DIODE-ZENER-0805"))
    )
    (comp (ref "D2")
      (value "5v")
      (footprint "eagle-import:SOD-323")
      (libsource (lib "eagle-import") (part "DIODE-ZENER-0805"))
    )
    (comp (ref "D3")
      (value "5v")
      (footprint "eagle-import:SOD-323")
      (libsource (lib "eagle-import") (part "DIODE-ZENER-0805"))
    )
    (comp (ref "F1")
      (value "FUSE-HOLDER-3557-2")
      (footprint "eagle-import:3557-2")
      (libsource (lib "eagle-import") (part "FUSE-HOLDER-3557-2"))
    )
    (comp (ref "J1")
      (value "CONN-02-3.81MM-PLUGIN-SCREW")
      (footprint "eagle-import:CONN-3.81MM-KF2EDG-2")
      (libsource (lib "eagle-import") (part "CONN-02-3.81MM-PLUGIN-SCREW"))
    )
    (comp (ref "J2")
      (value "CONN-02-3.81MM-PLUGIN-SCREW")
      (footprint "eagle-import:CONN-3.81MM-KF2EDG-2")
      (libsource (lib "eagle-import") (part "CONN-02-3.81MM-PLUGIN-SCREW"))
    )
    (comp (ref "M1")
      (value "METER-PANEL-ANALOG-CURRENT-PLUGIN-3.81MM")
      (footprint "eagle-import:CONN-3.81MM-KF2EDG-2")
      (libsource (lib "eagle-import") (part "METER-PANEL-ANALOG-CURRENT-PLUGIN-3.81MM"))
    )
    (comp (ref "M2")
      (value "METER-PANEL-ANALOG-VOLTAGE-PLUGIN-3.81MM")
      (footprint "eagle-import:CONN-3.81MM-KF2EDG-2")
      (libsource (lib "eagle-import") (part "METER-PANEL-ANALOG-VOLTAGE-PLUGIN-3.81MM"))
    )
    (comp (ref "Q1")
      (value "STN1HNK60")
      (footprint "eagle-import:SOT23-3")
      (libsource (lib "eagle-import") (part "FET-NCH-SOT23"))
    )
    (comp (ref "Q2")
      (value "FET-NCH-TO252")
      (footprint "eagle-import:TO252")
      (libsource (lib "eagle-import") (part "FET-NCH-TO252"))
    )
    (comp (ref "Q3")
      (value "BC337")
      (footprint "eagle-import:SOT23-3")
      (libsource (lib "eagle-import") (part "TRANSISTOR_NPNSOT23-3"))
    )
    (comp (ref "R1")
      (value "1M")
      (footprint "eagle-import:R2512")
      (fields (field (name "DESC") "1W"))
      (libsource (lib "eagle-import") (part "R-2512"))
    )
    (comp (ref "R2")
      (value "470k")
      (footprint "eagle-import:R2512")
      (libsource (lib "eagle-import") (part "R-2512"))
    )
    (comp (ref "R3")
      (value "3.3")
      (footprint "eagle-import:R2512")
      (libsource (lib "eagle-import") (part "R-2512"))
    )
    (comp (ref "R4")
      (value "10M")
      (footprint "eagle-import:R2512")
      (fields (field (name "DESC") ".1%"))
      (libsource (lib "eagle-import") (part "R-2512"))
    )
    (comp (ref "R5")
      (value "83k")
      (footprint "eagle-import:R2512")
      (fields (field (name "DESC") ".1%"))
      (libsource (lib "eagle-import") (part "R-2512"))
    )
    (comp (ref "R6")
      (value "10M")
      (footprint "eagle-import:R2512")
      (fields (field (name "DESC") ",1%"))
      (libsource (lib "eagle-import") (part "R-2512"))
    )
    (comp (ref "R7")
      (value "83k")
      (footprint "eagle-import:R2512")
      (fields (field (name "DESC") ".1%"))
      (libsource (lib "eagle-import") (part "R-2512"))
    )
    (comp (ref "U1")
      (value "AMP-OPAMP-DUAL-SO08")
      (footprint "eagle-import:SO08")
      (libsource (lib "eagle-import") (part "AMP-OPAMP-DUAL-SO08"))
    )
  )
  (nets
    (net (code "2") (name "FROMDAC") (class "Default")
      (node (ref "Q1") (pin "1") (pinfunction "G_1") (pintype "passive"))
    )
    (net (code "3") (name "GND") (class "Default")
      (node (ref "C1") (pin "-") (pinfunction "2_-") (pintype "passive"))
      (node (ref "D2") (pin "A") (pinfunction "A_A") (pintype "passive"))
      (node (ref "D3") (pin "A") (pinfunction "A_A") (pintype "passive"))
      (node (ref "GGND") (pin "1") (pinfunction "P$1_1") (pintype "bidirectional"))
      (node (ref "GND") (pin "1") (pinfunction "P$1_1") (pintype "bidirectional"))
      (node (ref "GND19") (pin "1") (pinfunction "P$1_1") (pintype "bidirectional"))
      (node (ref "GND21") (pin "1") (pinfunction "P$1_1") (pintype "bidirectional"))
      (node (ref "GND23") (pin "1") (pinfunction "P$1_1") (pintype "bidirectional"))
      (node (ref "GND25") (pin "1") (pinfunction "P$1_1") (pintype "bidirectional"))
      (node (ref "J1") (pin "1") (pinfunction "1_1") (pintype "passive"))
      (node (ref "J10") (pin "1") (pinfunction "1_1") (pintype "passive"))
      (node (ref "J11") (pin "1") (pinfunction "1_1") (pintype "passive"))
      (node (ref "J12") (pin "1") (pinfunction "1_1") (pintype "passive"))
      (node (ref "J13") (pin "1") (pinfunction "1_1") (pintype "passive"))
      (node (ref "J18") (pin "1") (pinfunction "GND_1") (pintype "bidirectional"))
      (node (ref "J2") (pin "1") (pinfunction "1_1") (pintype "passive"))
      (node (ref "J3") (pin "1") (pinfunction "GND_1") (pintype "bidirectional"))
      (node (ref "J4") (pin "1") (pinfunction "GND_1") (pintype "bidirectional"))
      (node (ref "J5") (pin "1") (pinfunction "GND_1") (pintype "bidirectional"))
      (node (ref "J9") (pin "1") (pinfunction "1_1") (pintype "passive"))
      (node (ref "M2") (pin "1") (pinfunction "-_1") (pintype "bidirectional"))
      (node (ref "PGND") (pin "1") (pinfunction "P$1_1") (pintype "bidirectional"))
      (node (ref "Q1") (pin "2") (pinfunction "S_2") (pintype "passive"))
      (node (ref "R5") (pin "1") (pinfunction "1_1") (pintype "passive"))
      (node (ref "R7") (pin "1") (pinfunction "1_1") (pintype "passive"))
      (node (ref "SGND") (pin "1") (pinfunction "P$1_1") (pintype "bidirectional"))
      (node (ref "U$1") (pin "1") (pinfunction "GND_1") (pintype "bidirectional"))
      (node (ref "U$2") (pin "1") (pinfunction "GND_1") (pintype "bidirectional"))
      (node (ref "U$3") (pin "1") (pinfunction "GND_1") (pintype "bidirectional"))
      (node (ref "U$4") (pin "1") (pinfunction "GND_1") (pintype "bidirectional"))
    )
    (net (code "4") (name "N$8") (class "Default")
      (node (ref "D3") (pin "C") (pinfunction "C_C") (pintype "passive"))
      (node (ref "R6") (pin "1") (pinfunction "1_1") (pintype "passive"))
      (node (ref "R7") (pin "2") (pinfunction "2_2") (pintype "passive"))
      (node (ref "U1") (pin "5") (pinfunction "+IN_5") (pintype "input"))
    )
    (net (code "5") (name "N$9") (class "Default")
      (node (ref "U1") (pin "7") (pinfunction "OUT_7") (pintype "output"))
    )
    (net (code "7") (name "NEUTRAL") (class "Default")
      (node (ref "GL1") (pin "2") (pinfunction "A1_2") (pintype "passive"))
      (node (ref "GL2") (pin "2") (pinfunction "A1_2") (pintype "passive"))
      (node (ref "GL3") (pin "2") (pinfunction "A1_2") (pintype "passive"))
      (node (ref "GL4") (pin "2") (pinfunction "A1_2") (pintype "passive"))
      (node (ref "GL5") (pin "2") (pinfunction "A1_2") (pintype "passive"))
      (node (ref "J10") (pin "2") (pinfunction "2_2") (pintype "passive"))
      (node (ref "J11") (pin "2") (pinfunction "2_2") (pintype "passive"))
      (node (ref "J12") (pin "2") (pinfunction "2_2") (pintype "passive"))
      (node (ref "J13") (pin "2") (pinfunction "2_2") (pintype "passive"))
      (node (ref "J15") (pin "1") (pinfunction "1_1") (pintype "passive"))
      (node (ref "J16") (pin "1") (pinfunction "1_1") (pintype "passive"))
      (node (ref "J17") (pin "1") (pinfunction "1_1") (pintype "passive"))
      (node (ref "J18") (pin "2") (pinfunction "NEU_2") (pintype "bidirectional"))
      (node (ref "J3") (pin "2") (pinfunction "NEU_2") (pintype "bidirectional"))
      (node (ref "J5") (pin "2") (pinfunction "NEU_2") (pintype "bidirectional"))
      (node (ref "J6") (pin "2") (pinfunction "P$2_2") (pintype "bidirectional"))
      (node (ref "J9") (pin "2") (pinfunction "2_2") (pintype "passive"))
      (node (ref "M4") (pin "1") (pinfunction "-_1") (pintype "bidirectional"))
      (node (ref "NEUTRAL") (pin "1") (pinfunction "P$1_1") (pintype "bidirectional"))
      (node (ref "T1") (pin "2") (pinfunction "P2_2") (pintype "passive"))
      (node (ref "T100") (pin "2") (pinfunction "S2_2") (pintype "passive"))
      (node (ref "T1000") (pin "2") (pinfunction "S2_2") (pintype "passive"))
      (node (ref "T12.6") (pin "2") (pinfunction "S2_2") (pintype "passive"))
      (node (ref "T120") (pin "2") (pinfunction "P2_2") (pintype "passive"))
      (node (ref "T2") (pin "2") (pinfunction "P2_2") (pintype "passive"))
      (node (ref "T5.0") (pin "2") (pinfunction "S2_2") (pintype "passive"))
      (node (ref "T6.3") (pin "2") (pinfunction "S2_2") (pintype "passive"))
      (node (ref "T600") (pin "2") (pinfunction "S2_2") (pintype "passive"))
      (node (ref "U$1") (pin "2") (pinfunction "NEU_2") (pintype "bidirectional"))
      (node (ref "U$2") (pin "2") (pinfunction "NEU_2") (pintype "bidirectional"))
      (node (ref "U$3") (pin "2") (pinfunction "NEU_2") (pintype "bidirectional"))
      (node (ref "U$4") (pin "2") (pinfunction "NEU_2") (pintype "bidirectional"))
    )
    (net (code "8") (name "Net-(BF1-P$1)") (class "Default")
      (node (ref "BF1") (pin "1") (pinfunction "P$1_1") (pintype "bidirectional"))
      (node (ref "C9") (pin "+") (pinfunction "+_+") (pintype "passive"))
      (node (ref "D6") (pin "C") (pinfunction "C_C") (pintype "bidirectional"))
      (node (ref "D7") (pin "C") (pinfunction "C_C") (pintype "bidirectional"))
      (node (ref "R15") (pin "2") (pinfunction "2_2") (pintype "passive"))
    )
    (net (code "9") (name "Net-(BF2-P$1)") (class "Default")
      (node (ref "BF2") (pin "1") (pinfunction "P$1_1") (pintype "bidirectional"))
      (node (ref "C11") (pin "+") (pinfunction "+_+") (pintype "passive"))
      (node (ref "R15") (pin "1") (pinfunction "1_1") (pintype "passive"))
      (node (ref "R20") (pin "3") (pinfunction "2_3") (pintype "passive"))
      (node (ref "R24") (pin "2") (pinfunction "2_2") (pintype "passive"))
    )
    (net (code "10") (name "Net-(BF3-P$1)") (class "Default")
      (node (ref "BF3") (pin "1") (pinfunction "P$1_1") (pintype "bidirectional"))
      (node (ref "C10") (pin "-") (pinfunction "-_-") (pintype "passive"))
      (node (ref "D4") (pin "A") (pinfunction "A_A") (pintype "bidirectional"))
      (node (ref "D5") (pin "A") (pinfunction "A_A") (pintype "bidirectional"))
      (node (ref "R18") (pin "2") (pinfunction "2_2") (pintype "passive"))
    )
    (net (code "11") (name "Net-(BF4-P$1)") (class "Default")
      (node (ref "BF4") (pin "1") (pinfunction "P$1_1") (pintype "bidirectional"))
      (node (ref "C7") (pin "-") (pinfunction "-_-") (pintype "passive"))
      (node (ref "R18") (pin "1") (pinfunction "1_1") (pintype "passive"))
      (node (ref "R20") (pin "1") (pinfunction "1_1") (pintype "passive"))
      (node (ref "R25") (pin "1") (pinfunction "1_1") (pintype "passive"))
    )
    (net (code "12") (name "Net-(BF5-P$1)") (class "Default")
      (node (ref "BF5") (pin "1") (pinfunction "P$1_1") (pintype "bidirectional"))
      (node (ref "M10") (pin "2") (pinfunction "+_2") (pintype "bidirectional"))
      (node (ref "R21") (pin "2") (pinfunction "2_2") (pintype "passive"))
      (node (ref "R23") (pin "2") (pinfunction "2_2") (pintype "passive"))
    )
    (net (code "13") (name "Net-(BF6-P$1)") (class "Default")
      (node (ref "BF6") (pin "1") (pinfunction "P$1_1") (pintype "bidirectional"))
      (node (ref "GRIDOUT+") (pin "1") (pinfunction "P$1_1") (pintype "bidirectional"))
      (node (ref "M9") (pin "1") (pinfunction "-_1") (pintype "bidirectional"))
      (node (ref "S17") (pin "2") (pinfunction "2_2") (pintype "passive"))
      (node (ref "S18") (pin "2") (pinfunction "2_2") (pintype "passive"))
      (node (ref "S20") (pin "2") (pinfunction "2_2") (pintype "passive"))
    )
    (net (code "14") (name "Net-(C1-1)") (class "Default")
      (node (ref "C1") (pin "+") (pinfunction "1_+") (pintype "passive"))
      (node (ref "M1") (pin "2") (pinfunction "+_2") (pintype "bidirectional"))
      (node (ref "Q3") (pin "2") (pinfunction "E_2") (pintype "passive"))
      (node (ref "R3") (pin "2") (pinfunction "2_2") (pintype "passive"))
      (node (ref "R6") (pin "2") (pinfunction "2_2") (pintype "passive"))
    )
    (net (code "15") (name "Net-(C2-Pad+)") (class "Default")
      (node (ref "C2") (pin "+") (pinfunction "+_+") (pintype "passive"))
      (node (ref "R10") (pin "2") (pinfunction "2_2") (pintype "passive"))
      (node (ref "S3") (pin "2") (pinfunction "2_2") (pintype "passive"))
    )
    (net (code "16") (name "Net-(C2-Pad-)") (class "Default")
      (node (ref "C2") (pin "-") (pinfunction "-_-") (pintype "passive"))
      (node (ref "C3") (pin "+") (pinfunction "+_+") (pintype "passive"))
      (node (ref "R10") (pin "1") (pinfunction "1_1") (pintype "passive"))
      (node (ref "R11") (pin "2") (pinfunction "2_2") (pintype "passive"))
    )
    (net (code "17") (name "Net-(C4-Pad+)") (class "Default")
      (node (ref "C4") (pin "+") (pinfunction "+_+") (pintype "passive"))
      (node (ref "R13") (pin "2") (pinfunction "2_2") (pintype "passive"))
      (node (ref "S7") (pin "2") (pinfunction "2_2") (pintype "passive"))
    )
    (net (code "18") (name "Net-(C4-Pad-)") (class "Default")
      (node (ref "C4") (pin "-") (pinfunction "-_-") (pintype "passive"))
      (node (ref "C5") (pin "+") (pinfunction "+_+") (pintype "passive"))
      (node (ref "R13") (pin "1") (pinfunction "1_1") (pintype "passive"))
      (node (ref "R14") (pin "2") (pinfunction "2_2") (pintype "passive"))
    )
    (net (code "19") (name "Net-(C6-Pad+)") (class "Default")
      (node (ref "C6") (pin "+") (pinfunction "+_+") (pintype "passive"))
      (node (ref "R9") (pin "2") (pinfunction "2_2") (pintype "passive"))
      (node (ref "S8") (pin "2") (pinfunction "2_2") (pintype "passive"))
    )
    (net (code "20") (name "Net-(C8-Pad+)") (class "Default")
      (node (ref "C8") (pin "+") (pinfunction "+_+") (pintype "passive"))
      (node (ref "R17") (pin "2") (pinfunction "2_2") (pintype "passive"))
      (node (ref "S12") (pin "2") (pinfunction "2_2") (pintype "passive"))
    )
    (net (code "21") (name "Net-(F1-P$1-Pad1@1)") (class "Default")
      (node (ref "F1") (pin "1@1") (pinfunction "P$1_1@1") (pintype "bidirectional"))
      (node (ref "F1") (pin "1@2") (pinfunction "P$1_1@2") (pintype "bidirectional"))
      (node (ref "J2") (pin "2") (pinfunction "2_2") (pintype "passive"))
    )
    (net (code "22") (name "Net-(F2-P$1-Pad1@1)") (class "Default")
      (node (ref "F2") (pin "1@1") (pinfunction "P$1_1@1") (pintype "bidirectional"))
      (node (ref "F2") (pin "1@2") (pinfunction "P$1_1@2") (pintype "bidirectional"))
      (node (ref "J12") (pin "3") (pinfunction "3_3") (pintype "passive"))
    )
    (net (code "23") (name "Net-(F2-P$2-Pad2@1)") (class "Default")
      (node (ref "F2") (pin "2@1") (pinfunction "P$2_2@1") (pintype "bidirectional"))
      (node (ref "F2") (pin "2@2") (pinfunction "P$2_2@2") (pintype "bidirectional"))
      (node (ref "S1") (pin "1") (pinfunction "1_1") (pintype "passive"))
    )
    (net (code "24") (name "Net-(F3-P$1-Pad1@1)") (class "Default")
      (node (ref "F3") (pin "1@1") (pinfunction "P$1_1@1") (pintype "bidirectional"))
      (node (ref "F3") (pin "1@2") (pinfunction "P$1_1@2") (pintype "bidirectional"))
      (node (ref "J9") (pin "3") (pinfunction "3_3") (pintype "passive"))
    )
    (net (code "25") (name "Net-(F3-P$2-Pad2@1)") (class "Default")
      (node (ref "F3") (pin "2@1") (pinfunction "P$2_2@1") (pintype "bidirectional"))
      (node (ref "F3") (pin "2@2") (pinfunction "P$2_2@2") (pintype "bidirectional"))
      (node (ref "S15") (pin "1") (pinfunction "1_1") (pintype "passive"))
    )
    (net (code "26") (name "Net-(F4-P$1-Pad1@1)") (class "Default")
      (node (ref "F4") (pin "1@1") (pinfunction "P$1_1@1") (pintype "bidirectional"))
      (node (ref "F4") (pin "1@2") (pinfunction "P$1_1@2") (pintype "bidirectional"))
      (node (ref "J11") (pin "3") (pinfunction "3_3") (pintype "passive"))
    )
    (net (code "27") (name "Net-(F4-P$2-Pad2@1)") (class "Default")
      (node (ref "F4") (pin "2@1") (pinfunction "P$2_2@1") (pintype "bidirectional"))
      (node (ref "F4") (pin "2@2") (pinfunction "P$2_2@2") (pintype "bidirectional"))
      (node (ref "S13") (pin "1") (pinfunction "1_1") (pintype "passive"))
    )
    (net (code "28") (name "Net-(F5-P$1-Pad1@1)") (class "Default")
      (node (ref "F5") (pin "1@1") (pinfunction "P$1_1@1") (pintype "bidirectional"))
      (node (ref "F5") (pin "1@2") (pinfunction "P$1_1@2") (pintype "bidirectional"))
      (node (ref "J13") (pin "3") (pinfunction "3_3") (pintype "passive"))
    )
    (net (code "29") (name "Net-(F5-P$2-Pad2@1)") (class "Default")
      (node (ref "F5") (pin "2@1") (pinfunction "P$2_2@1") (pintype "bidirectional"))
      (node (ref "F5") (pin "2@2") (pinfunction "P$2_2@2") (pintype "bidirectional"))
      (node (ref "S14") (pin "1") (pinfunction "1_1") (pintype "passive"))
    )
    (net (code "30") (name "Net-(F5A-P$1)") (class "Default")
      (node (ref "F5A") (pin "1") (pinfunction "P$1_1") (pintype "bidirectional"))
      (node (ref "T5.0") (pin "5") (pinfunction "P2_5") (pintype "passive"))
    )
    (net (code "31") (name "Net-(F5B-P$1)") (class "Default")
      (node (ref "F5B") (pin "1") (pinfunction "P$1_1") (pintype "bidirectional"))
      (node (ref "T5.0") (pin "3") (pinfunction "P1_3") (pintype "passive"))
    )
    (net (code "32") (name "Net-(F5CT-P$1)") (class "Default")
      (node (ref "F5CT") (pin "1") (pinfunction "P$1_1") (pintype "bidirectional"))
      (node (ref "T5.0") (pin "4") (pinfunction "PCT_4") (pintype "passive"))
    )
    (net (code "33") (name "Net-(F6-P$1-Pad1@1)") (class "Default")
      (node (ref "F6") (pin "1@1") (pinfunction "P$1_1@1") (pintype "bidirectional"))
      (node (ref "F6") (pin "1@2") (pinfunction "P$1_1@2") (pintype "bidirectional"))
      (node (ref "J10") (pin "3") (pinfunction "3_3") (pintype "passive"))
    )
    (net (code "34") (name "Net-(F6-P$2-Pad2@1)") (class "Default")
      (node (ref "F6") (pin "2@1") (pinfunction "P$2_2@1") (pintype "bidirectional"))
      (node (ref "F6") (pin "2@2") (pinfunction "P$2_2@2") (pintype "bidirectional"))
      (node (ref "S2") (pin "1") (pinfunction "1_1") (pintype "passive"))
    )
    (net (code "35") (name "Net-(F6.3A-P$1)") (class "Default")
      (node (ref "F6.3A") (pin "1") (pinfunction "P$1_1") (pintype "bidirectional"))
      (node (ref "T6.3") (pin "5") (pinfunction "P2_5") (pintype "passive"))
    )
    (net (code "36") (name "Net-(F6.3B-P$1)") (class "Default")
      (node (ref "F6.3B") (pin "1") (pinfunction "P$1_1") (pintype "bidirectional"))
      (node (ref "T6.3") (pin "3") (pinfunction "P1_3") (pintype "passive"))
    )
    (net (code "37") (name "Net-(F6.3CT-P$1)") (class "Default")
      (node (ref "F6.3CT") (pin "1") (pinfunction "P$1_1") (pintype "bidirectional"))
      (node (ref "T6.3") (pin "4") (pinfunction "PCT_4") (pintype "passive"))
    )
    (net (code "38") (name "Net-(F12.6A-P$1)") (class "Default")
      (node (ref "F12.6A") (pin "1") (pinfunction "P$1_1") (pintype "bidirectional"))
      (node (ref "T12.6") (pin "5") (pinfunction "P2_5") (pintype "passive"))
    )
    (net (code "39") (name "Net-(F12.6B-P$1)") (class "Default")
      (node (ref "F12.6B") (pin "1") (pinfunction "P$1_1") (pintype "bidirectional"))
      (node (ref "T12.6") (pin "3") (pinfunction "P1_3") (pintype "passive"))
    )
    (net (code "40") (name "Net-(F12.6CT-P$1)") (class "Default")
      (node (ref "F12.6CT") (pin "1") (pinfunction "P$1_1") (pintype "bidirectional"))
      (node (ref "T12.6") (pin "4") (pinfunction "PCT_4") (pintype "passive"))
    )
    (net (code "41") (name "Net-(GL1-A)") (class "Default")
      (node (ref "GL1") (pin "1") (pinfunction "A_1") (pintype "passive"))
      (node (ref "S19") (pin "1") (pinfunction "1_1") (pintype "passive"))
      (node (ref "S2") (pin "2") (pinfunction "2_2") (pintype "passive"))
      (node (ref "T1") (pin "1") (pinfunction "P1_1") (pintype "passive"))
    )
    (net (code "42") (name "Net-(GL2-A)") (class "Default")
      (node (ref "GL2") (pin "1") (pinfunction "A_1") (pintype "passive"))
      (node (ref "M3") (pin "2") (pinfunction "+_2") (pintype "bidirectional"))
      (node (ref "S1") (pin "2") (pinfunction "2_2") (pintype "passive"))
    )
    (net (code "43") (name "Net-(GL3-A)") (class "Default")
      (node (ref "GL3") (pin "1") (pinfunction "A_1") (pintype "passive"))
      (node (ref "S13") (pin "2") (pinfunction "2_2") (pintype "passive"))
      (node (ref "S16") (pin "1") (pinfunction "1_1") (pintype "passive"))
      (node (ref "T2") (pin "1") (pinfunction "P1_1") (pintype "passive"))
    )
    (net (code "44") (name "Net-(GL4-A)") (class "Default")
      (node (ref "GL4") (pin "1") (pinfunction "A_1") (pintype "passive"))
      (node (ref "S14") (pin "2") (pinfunction "2_2") (pintype "passive"))
      (node (ref "T100") (pin "1") (pinfunction "S1_1") (pintype "passive"))
    )
    (net (code "45") (name "Net-(GL5-A)") (class "Default")
      (node (ref "GL5") (pin "1") (pinfunction "A_1") (pintype "passive"))
      (node (ref "S15") (pin "2") (pinfunction "2_2") (pintype "passive"))
      (node (ref "T12.6") (pin "1") (pinfunction "S1_1") (pintype "passive"))
      (node (ref "T5.0") (pin "1") (pinfunction "S1_1") (pintype "passive"))
      (node (ref "T6.3") (pin "1") (pinfunction "S1_1") (pintype "passive"))
    )
    (net (code "46") (name "Net-(GRIDOUT--P$1)") (class "Default")
      (node (ref "C10") (pin "+") (pinfunction "+_+") (pintype "passive"))
      (node (ref "C11") (pin "-") (pinfunction "-_-") (pintype "passive"))
      (node (ref "C7") (pin "+") (pinfunction "+_+") (pintype "passive"))
      (node (ref "C9") (pin "-") (pinfunction "-_-") (pintype "passive"))
      (node (ref "GRIDOUT-") (pin "1") (pinfunction "P$1_1") (pintype "bidirectional"))
      (node (ref "M9") (pin "2") (pinfunction "+_2") (pintype "bidirectional"))
      (node (ref "R24") (pin "1") (pinfunction "1_1") (pintype "passive"))
      (node (ref "R25") (pin "2") (pinfunction "2_2") (pintype "passive"))
      (node (ref "T100") (pin "4") (pinfunction "PCT_4") (pintype "passive"))
    )
    (net (code "47") (name "Net-(J4-LINE)") (class "Default")
      (node (ref "J4") (pin "3") (pinfunction "LINE_3") (pintype "bidirectional"))
      (node (ref "T120") (pin "5") (pinfunction "S1_5") (pintype "passive"))
    )
    (net (code "48") (name "Net-(J4-NEU)") (class "Default")
      (node (ref "J4") (pin "2") (pinfunction "NEU_2") (pintype "bidirectional"))
      (node (ref "T120") (pin "6") (pinfunction "S2_6") (pintype "passive"))
    )
    (net (code "49") (name "Net-(J7-P$1)") (class "Default")
      (node (ref "J7") (pin "1") (pinfunction "P$1_1") (pintype "bidirectional"))
      (node (ref "PF1") (pin "1") (pinfunction "P$1_1") (pintype "bidirectional"))
      (node (ref "PF3") (pin "1") (pinfunction "P$1_1") (pintype "bidirectional"))
      (node (ref "PRECT") (pin "1") (pinfunction "P$1_1") (pintype "bidirectional"))
      (node (ref "S3") (pin "1") (pinfunction "1_1") (pintype "passive"))
      (node (ref "S4") (pin "1") (pinfunction "1_1") (pintype "passive"))
      (node (ref "S5") (pin "1") (pinfunction "1_1") (pintype "passive"))
      (node (ref "S6") (pin "1") (pinfunction "1_1") (pintype "passive"))
    )
    (net (code "50") (name "Net-(J7-P$2)") (class "Default")
      (node (ref "C3") (pin "-") (pinfunction "-_-") (pintype "passive"))
      (node (ref "C5") (pin "-") (pinfunction "-_-") (pintype "passive"))
      (node (ref "J7") (pin "2") (pinfunction "P$2_2") (pintype "bidirectional"))
      (node (ref "M6") (pin "1") (pinfunction "-_1") (pintype "bidirectional"))
      (node (ref "PLATEOUT-") (pin "1") (pinfunction "P$1_1") (pintype "bidirectional"))
      (node (ref "R11") (pin "1") (pinfunction "1_1") (pintype "passive"))
      (node (ref "R14") (pin "1") (pinfunction "1_1") (pintype "passive"))
      (node (ref "T1000") (pin "4") (pinfunction "PCT_4") (pintype "passive"))
    )
    (net (code "51") (name "Net-(J8-P$1)") (class "Default")
      (node (ref "J8") (pin "1") (pinfunction "P$1_1") (pintype "bidirectional"))
      (node (ref "S10") (pin "1") (pinfunction "1_1") (pintype "passive"))
      (node (ref "S11") (pin "1") (pinfunction "1_1") (pintype "passive"))
      (node (ref "S8") (pin "1") (pinfunction "1_1") (pintype "passive"))
      (node (ref "S9") (pin "1") (pinfunction "1_1") (pintype "passive"))
      (node (ref "SF1") (pin "1") (pinfunction "P$1_1") (pintype "bidirectional"))
      (node (ref "SF3") (pin "1") (pinfunction "P$1_1") (pintype "bidirectional"))
      (node (ref "SRECT") (pin "1") (pinfunction "P$1_1") (pintype "bidirectional"))
    )
    (net (code "52") (name "Net-(J8-P$2)") (class "Default")
      (node (ref "C6") (pin "-") (pinfunction "-_-") (pintype "passive"))
      (node (ref "C8") (pin "-") (pinfunction "-_-") (pintype "passive"))
      (node (ref "J8") (pin "2") (pinfunction "P$2_2") (pintype "bidirectional"))
      (node (ref "M8") (pin "1") (pinfunction "-_1") (pintype "bidirectional"))
      (node (ref "R17") (pin "1") (pinfunction "1_1") (pintype "passive"))
      (node (ref "R9") (pin "1") (pinfunction "1_1") (pintype "passive"))
      (node (ref "SCREENOUT-") (pin "1") (pinfunction "P$1_1") (pintype "bidirectional"))
      (node (ref "T600") (pin "4") (pinfunction "PCT_4") (pintype "passive"))
    )
    (net (code "53") (name "Net-(J15-2)") (class "Default")
      (node (ref "J15") (pin "3") (pinfunction "2_3") (pintype "passive"))
      (node (ref "J18") (pin "3") (pinfunction "LINE_3") (pintype "bidirectional"))
      (node (ref "J3") (pin "3") (pinfunction "LINE_3") (pintype "bidirectional"))
      (node (ref "LINE") (pin "1") (pinfunction "P$1_1") (pintype "bidirectional"))
      (node (ref "M3") (pin "1") (pinfunction "-_1") (pintype "bidirectional"))
      (node (ref "U$1") (pin "3") (pinfunction "LINE_3") (pintype "bidirectional"))
      (node (ref "U$2") (pin "3") (pinfunction "LINE_3") (pintype "bidirectional"))
      (node (ref "U$3") (pin "3") (pinfunction "LINE_3") (pintype "bidirectional"))
    )
    (net (code "54") (name "Net-(J15-W)") (class "Default")
      (node (ref "J15") (pin "2") (pinfunction "W_2") (pintype "passive"))
      (node (ref "J5") (pin "3") (pinfunction "LINE_3") (pintype "bidirectional"))
      (node (ref "J6") (pin "1") (pinfunction "P$1_1") (pintype "bidirectional"))
      (node (ref "LINEVAR") (pin "1") (pinfunction "P$1_1") (pintype "bidirectional"))
      (node (ref "M4") (pin "2") (pinfunction "+_2") (pintype "bidirectional"))
      (node (ref "T120") (pin "1") (pinfunction "P1_1") (pintype "passive"))
      (node (ref "U$4") (pin "3") (pinfunction "LINE_3") (pintype "bidirectional"))
    )
    (net (code "55") (name "Net-(J16-2)") (class "Default")
      (node (ref "J16") (pin "3") (pinfunction "2_3") (pintype "passive"))
      (node (ref "S19") (pin "2") (pinfunction "2_2") (pintype "passive"))
    )
    (net (code "56") (name "Net-(J16-W)") (class "Default")
      (node (ref "J16") (pin "2") (pinfunction "W_2") (pintype "passive"))
      (node (ref "T1000") (pin "1") (pinfunction "S1_1") (pintype "passive"))
    )
    (net (code "57") (name "Net-(J17-2)") (class "Default")
      (node (ref "J17") (pin "3") (pinfunction "2_3") (pintype "passive"))
      (node (ref "S16") (pin "2") (pinfunction "2_2") (pintype "passive"))
    )
    (net (code "58") (name "Net-(J17-W)") (class "Default")
      (node (ref "J17") (pin "2") (pinfunction "W_2") (pintype "passive"))
      (node (ref "T600") (pin "1") (pinfunction "S1_1") (pintype "passive"))
    )
    (net (code "59") (name "Net-(L1-P$1)") (class "Default")
      (node (ref "L1") (pin "1") (pinfunction "P$1_1") (pintype "passive"))
      (node (ref "M5") (pin "2") (pinfunction "+_2") (pintype "bidirectional"))
      (node (ref "PF2") (pin "1") (pinfunction "P$1_1") (pintype "bidirectional"))
      (node (ref "PF4") (pin "1") (pinfunction "P$1_1") (pintype "bidirectional"))
      (node (ref "R12") (pin "1") (pinfunction "1_1") (pintype "passive"))
      (node (ref "S6") (pin "2") (pinfunction "2_2") (pintype "passive"))
      (node (ref "S7") (pin "1") (pinfunction "1_1") (pintype "passive"))
    )
    (net (code "60") (name "Net-(L1-P$2)") (class "Default")
      (node (ref "L1") (pin "2") (pinfunction "P$2_2") (pintype "passive"))
      (node (ref "S4") (pin "2") (pinfunction "2_2") (pintype "passive"))
    )
    (net (code "61") (name "Net-(L2-P$1)") (class "Default")
      (node (ref "L2") (pin "1") (pinfunction "P$1_1") (pintype "passive"))
      (node (ref "M7") (pin "2") (pinfunction "+_2") (pintype "bidirectional"))
      (node (ref "R16") (pin "1") (pinfunction "1_1") (pintype "passive"))
      (node (ref "S11") (pin "2") (pinfunction "2_2") (pintype "passive"))
      (node (ref "S12") (pin "1") (pinfunction "1_1") (pintype "passive"))
      (node (ref "SF2") (pin "1") (pinfunction "P$1_1") (pintype "bidirectional"))
      (node (ref "SF4") (pin "1") (pinfunction "P$1_1") (pintype "bidirectional"))
    )
    (net (code "62") (name "Net-(L2-P$2)") (class "Default")
      (node (ref "L2") (pin "2") (pinfunction "P$2_2") (pintype "passive"))
      (node (ref "S9") (pin "2") (pinfunction "2_2") (pintype "passive"))
    )
    (net (code "63") (name "Net-(M1--)") (class "Default")
      (node (ref "J1") (pin "2") (pinfunction "2_2") (pintype "passive"))
      (node (ref "M1") (pin "1") (pinfunction "-_1") (pintype "bidirectional"))
      (node (ref "M2") (pin "2") (pinfunction "+_2") (pintype "bidirectional"))
      (node (ref "R4") (pin "2") (pinfunction "2_2") (pintype "passive"))
    )
    (net (code "64") (name "Net-(M5--)") (class "Default")
      (node (ref "M5") (pin "1") (pinfunction "-_1") (pintype "bidirectional"))
      (node (ref "M6") (pin "2") (pinfunction "+_2") (pintype "bidirectional"))
      (node (ref "PLATEOUT+") (pin "1") (pinfunction "P$1_1") (pintype "bidirectional"))
    )
    (net (code "65") (name "Net-(M7--)") (class "Default")
      (node (ref "M7") (pin "1") (pinfunction "-_1") (pintype "bidirectional"))
      (node (ref "M8") (pin "2") (pinfunction "+_2") (pintype "bidirectional"))
      (node (ref "SCREENOUT+") (pin "1") (pinfunction "P$1_1") (pintype "bidirectional"))
    )
    (net (code "66") (name "Net-(M10--)") (class "Default")
      (node (ref "M10") (pin "1") (pinfunction "-_1") (pintype "bidirectional"))
      (node (ref "S18") (pin "1") (pinfunction "1_1") (pintype "passive"))
    )
    (net (code "67") (name "Net-(PA-P$1)") (class "Default")
      (node (ref "PA") (pin "1") (pinfunction "P$1_1") (pintype "bidirectional"))
      (node (ref "T1000") (pin "3") (pinfunction "P1_3") (pintype "passive"))
    )
    (net (code "68") (name "Net-(PB-P$1)") (class "Default")
      (node (ref "PB") (pin "1") (pinfunction "P$1_1") (pintype "bidirectional"))
      (node (ref "T1000") (pin "5") (pinfunction "P2_5") (pintype "passive"))
    )
    (net (code "69") (name "Net-(PFA-P$1)") (class "Default")
      (node (ref "PFA") (pin "1") (pinfunction "P$1_1") (pintype "bidirectional"))
      (node (ref "T1") (pin "6") (pinfunction "S2_6") (pintype "passive"))
    )
    (net (code "70") (name "Net-(PFB-P$1)") (class "Default")
      (node (ref "PFB") (pin "1") (pinfunction "P$1_1") (pintype "bidirectional"))
      (node (ref "T1") (pin "5") (pinfunction "S1_5") (pintype "passive"))
    )
    (net (code "71") (name "Net-(Q1-D)") (class "Default")
      (node (ref "Q1") (pin "3") (pinfunction "D_3") (pintype "passive"))
      (node (ref "R1") (pin "1") (pinfunction "1_1") (pintype "passive"))
      (node (ref "R2") (pin "1") (pinfunction "1_1") (pintype "passive"))
    )
    (net (code "72") (name "Net-(Q2-D)") (class "Default")
      (node (ref "F1") (pin "2@1") (pinfunction "P$2_2@1") (pintype "bidirectional"))
      (node (ref "F1") (pin "2@2") (pinfunction "P$2_2@2") (pintype "bidirectional"))
      (node (ref "Q2") (pin "3") (pinfunction "D_3") (pintype "passive"))
      (node (ref "R1") (pin "2") (pinfunction "2_2") (pintype "passive"))
    )
    (net (code "73") (name "Net-(Q2-G)") (class "Default")
      (node (ref "D1") (pin "C") (pinfunction "C_C") (pintype "passive"))
      (node (ref "Q2") (pin "1") (pinfunction "G_1") (pintype "passive"))
      (node (ref "Q3") (pin "3") (pinfunction "C_3") (pintype "passive"))
      (node (ref "R2") (pin "2") (pinfunction "2_2") (pintype "passive"))
    )
    (net (code "74") (name "Net-(Q2-S)") (class "Default")
      (node (ref "D1") (pin "A") (pinfunction "A_A") (pintype "passive"))
      (node (ref "Q2") (pin "2") (pinfunction "S_2") (pintype "passive"))
      (node (ref "Q3") (pin "1") (pinfunction "B_1") (pintype "passive"))
      (node (ref "R3") (pin "1") (pinfunction "1_1") (pintype "passive"))
    )
    (net (code "75") (name "Net-(R12-Pad2)") (class "Default")
      (node (ref "R12") (pin "2") (pinfunction "2_2") (pintype "passive"))
      (node (ref "S5") (pin "2") (pinfunction "2_2") (pintype "passive"))
    )
    (net (code "76") (name "Net-(R16-Pad2)") (class "Default")
      (node (ref "R16") (pin "2") (pinfunction "2_2") (pintype "passive"))
      (node (ref "S10") (pin "2") (pinfunction "2_2") (pintype "passive"))
    )
    (net (code "77") (name "Net-(R21-Pad1)") (class "Default")
      (node (ref "R21") (pin "1") (pinfunction "1_1") (pintype "passive"))
      (node (ref "S17") (pin "1") (pinfunction "1_1") (pintype "passive"))
    )
    (net (code "78") (name "Net-(R23-Pad1)") (class "Default")
      (node (ref "R23") (pin "1") (pinfunction "1_1") (pintype "passive"))
      (node (ref "S20") (pin "1") (pinfunction "1_1") (pintype "passive"))
    )
    (net (code "79") (name "Net-(SA-P$1)") (class "Default")
      (node (ref "SA") (pin "1") (pinfunction "P$1_1") (pintype "bidirectional"))
      (node (ref "T600") (pin "3") (pinfunction "P1_3") (pintype "passive"))
    )
    (net (code "80") (name "Net-(SB-P$1)") (class "Default")
      (node (ref "SB") (pin "1") (pinfunction "P$1_1") (pintype "bidirectional"))
      (node (ref "T600") (pin "5") (pinfunction "P2_5") (pintype "passive"))
    )
    (net (code "81") (name "Net-(SFA-P$1)") (class "Default")
      (node (ref "SFA") (pin "1") (pinfunction "P$1_1") (pintype "bidirectional"))
      (node (ref "T2") (pin "6") (pinfunction "S2_6") (pintype "passive"))
    )
    (net (code "82") (name "Net-(SFB-P$1)") (class "Default")
      (node (ref "SFB") (pin "1") (pinfunction "P$1_1") (pintype "bidirectional"))
      (node (ref "T2") (pin "5") (pinfunction "S1_5") (pintype "passive"))
    )
    (net (code "83") (name "Net-(T100-P1)") (class "Default")
      (node (ref "D4") (pin "C") (pinfunction "C_C") (pintype "bidirectional"))
      (node (ref "D6") (pin "A") (pinfunction "A_A") (pintype "bidirectional"))
      (node (ref "T100") (pin "3") (pinfunction "P1_3") (pintype "passive"))
    )
    (net (code "84") (name "Net-(T100-P2)") (class "Default")
      (node (ref "D5") (pin "C") (pinfunction "C_C") (pintype "bidirectional"))
      (node (ref "D7") (pin "A") (pinfunction "A_A") (pintype "bidirectional"))
      (node (ref "T100") (pin "5") (pinfunction "P2_5") (pintype "passive"))
    )
    (net (code "86") (name "TOADC") (class "Default")
      (node (ref "D2") (pin "C") (pinfunction "C_C") (pintype "passive"))
      (node (ref "R4") (pin "1") (pinfunction "1_1") (pintype "passive"))
      (node (ref "R5") (pin "2") (pinfunction "2_2") (pintype "passive"))
      (node (ref "U1") (pin "6") (pinfunction "-IN_6") (pintype "input"))
    )
    (net (code "88") (name "V+") (class "Default")
      (node (ref "U1") (pin "8") (pinfunction "V+_8") (pintype "power_in"))
    )
    (net (code "89") (name "V-") (class "Default")
      (node (ref "U1") (pin "4") (pinfunction "V-_4") (pintype "power_in"))
    )
    (net (code "90") (name "unconnected-(F6.3A1-P$1-Pad1)") (class "Default")
      (node (ref "F6.3A1") (pin "1") (pinfunction "P$1_1") (pintype "bidirectional"))
    )
    (net (code "91") (name "unconnected-(F6.3A2-P$1-Pad1)") (class "Default")
      (node (ref "F6.3A2") (pin "1") (pinfunction "P$1_1") (pintype "bidirectional"))
    )
    (net (code "92") (name "unconnected-(F6.3B1-P$1-Pad1)") (class "Default")
      (node (ref "F6.3B1") (pin "1") (pinfunction "P$1_1") (pintype "bidirectional"))
    )
    (net (code "93") (name "unconnected-(F6.3B2-P$1-Pad1)") (class "Default")
      (node (ref "F6.3B2") (pin "1") (pinfunction "P$1_1") (pintype "bidirectional"))
    )
    (net (code "94") (name "unconnected-(J14-P$1-Pad1)") (class "Default")
      (node (ref "J14") (pin "1") (pinfunction "P$1_1") (pintype "bidirectional"))
    )
    (net (code "95") (name "unconnected-(J14-P$2-Pad2)") (class "Default")
      (node (ref "J14") (pin "2") (pinfunction "P$2_2") (pintype "bidirectional"))
    )
    (net (code "96") (name "unconnected-(PF5-P$1-Pad1)") (class "Default")
      (node (ref "PF5") (pin "1") (pinfunction "P$1_1") (pintype "bidirectional"))
    )
    (net (code "97") (name "unconnected-(R20-W-Pad2)") (class "Default")
      (node (ref "R20") (pin "2") (pinfunction "W_2") (pintype "passive"))
    )
    (net (code "98") (name "unconnected-(U1A-+IN-Pad3)") (class "Default")
      (node (ref "U1") (pin "3") (pinfunction "+IN_3") (pintype "input"))
    )
    (net (code "99") (name "unconnected-(U1A--IN-Pad2)") (class "Default")
      (node (ref "U1") (pin "2") (pinfunction "-IN_2") (pintype "input"))
    )
    (net (code "100") (name "unconnected-(U1A-OUT-Pad1)") (class "Default")
      (node (ref "U1") (pin "1") (pinfunction "OUT_1") (pintype "output"))
    )
  )
)
